# a130-8-octal-vca-expander.net
KiCad netlist of a schematic drawn in EAGLE
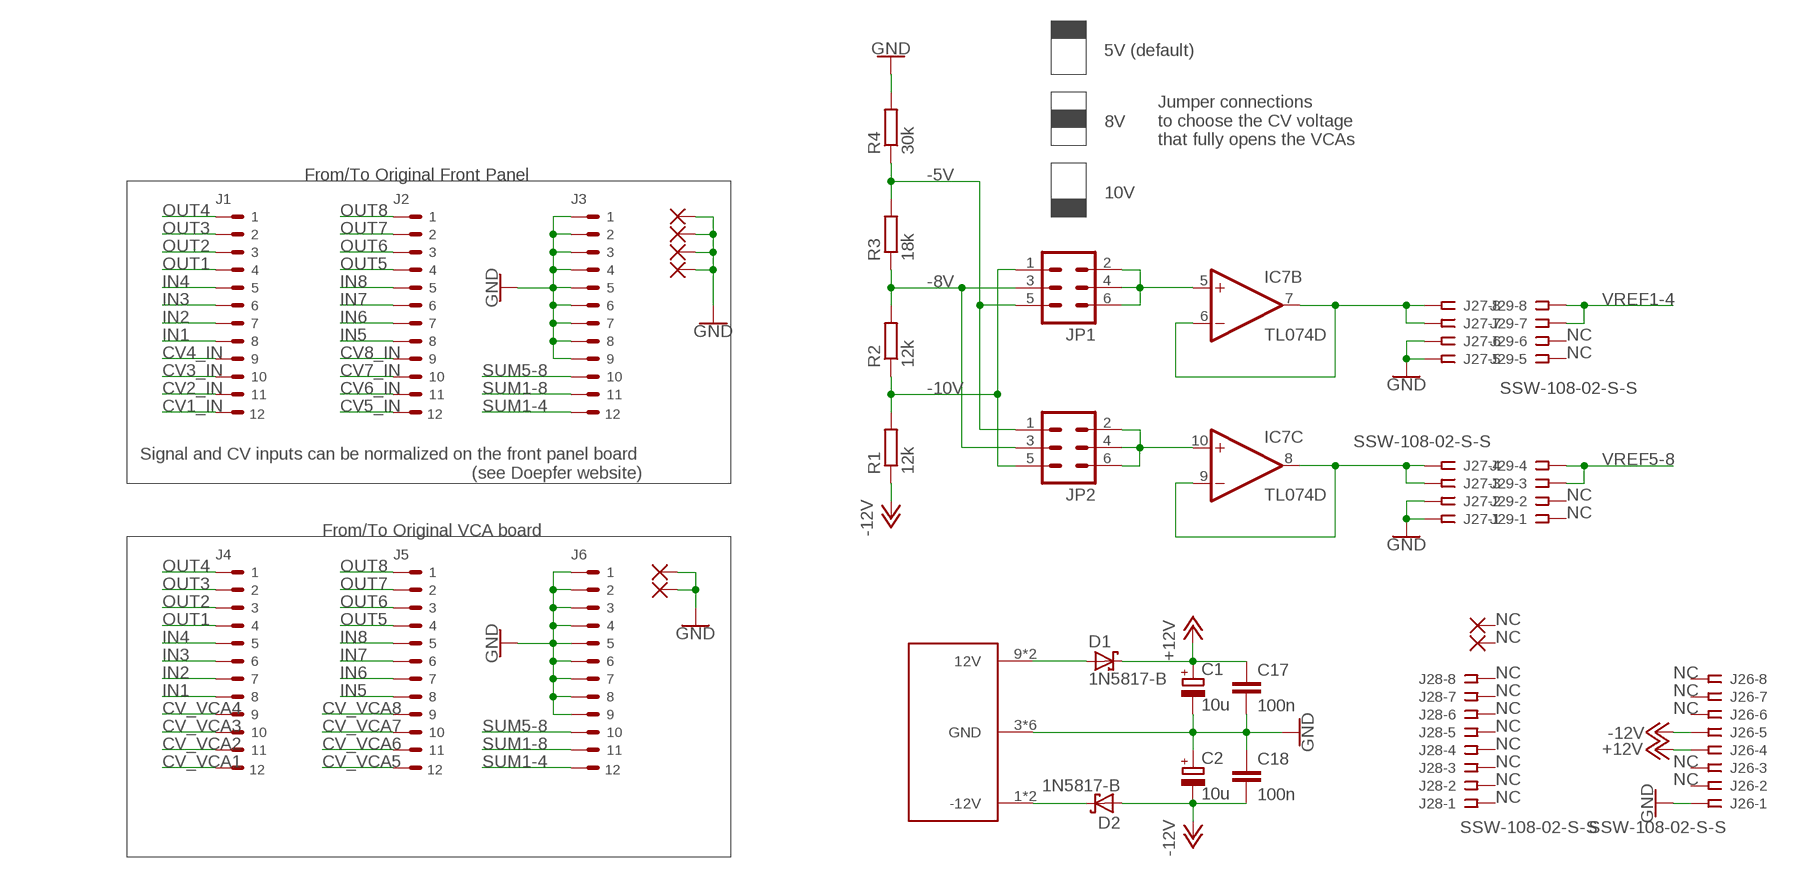
[diagram p0: schematic, sheet 1]
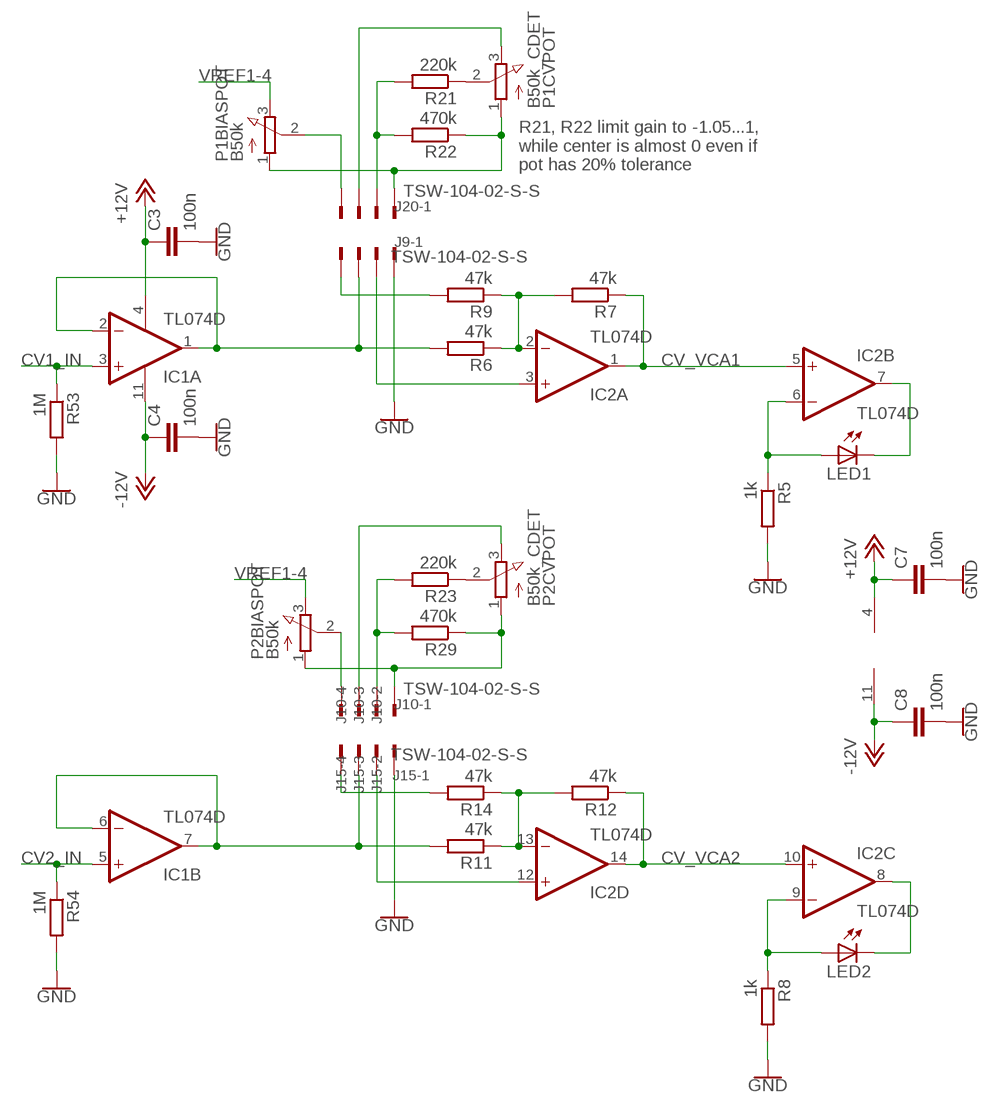
[diagram p1: schematic, sheet 2]
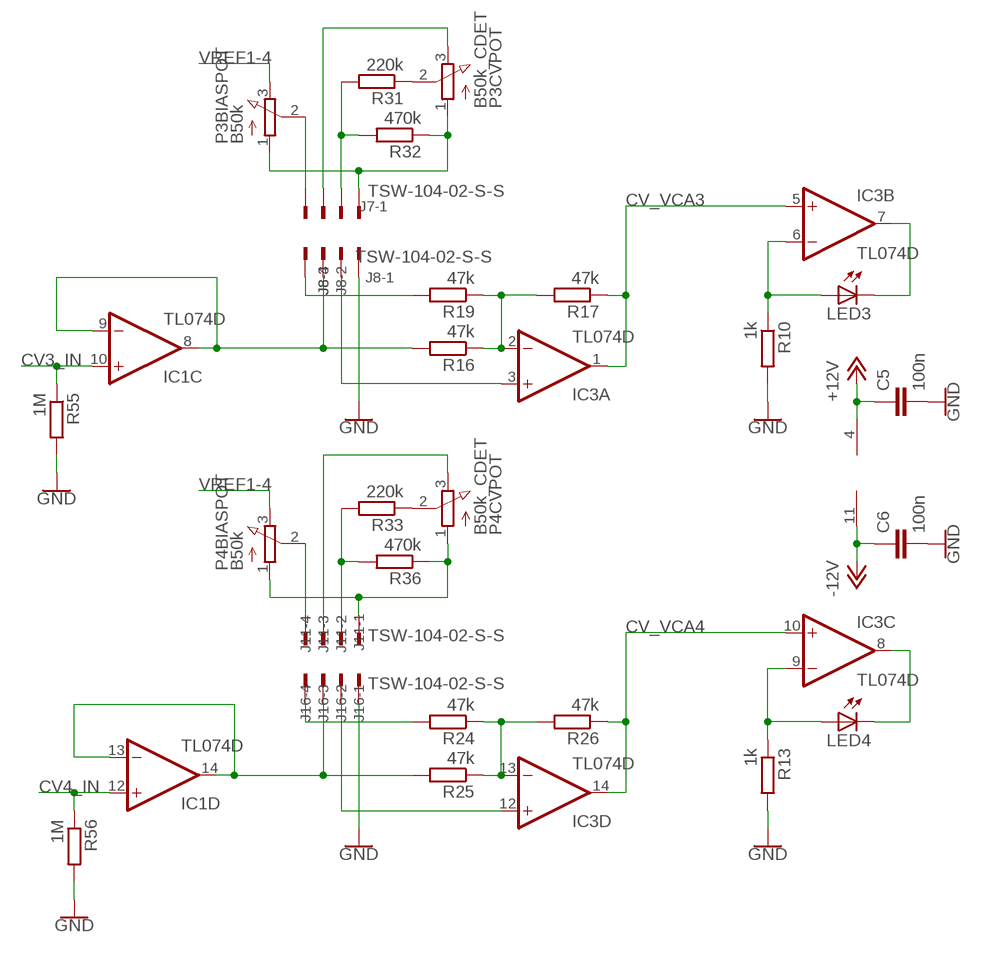
[diagram p2: schematic, sheet 3]
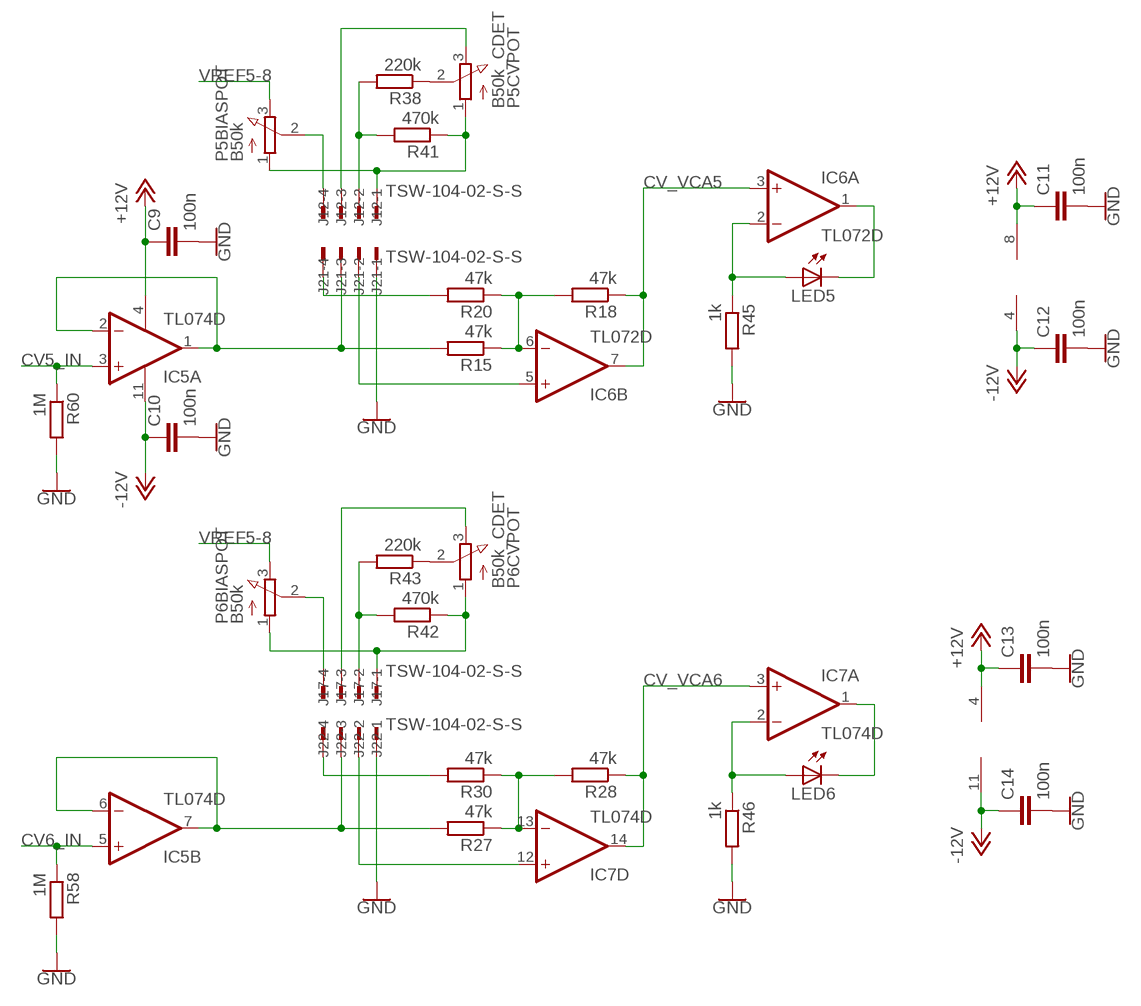
[diagram p3: schematic, sheet 4]
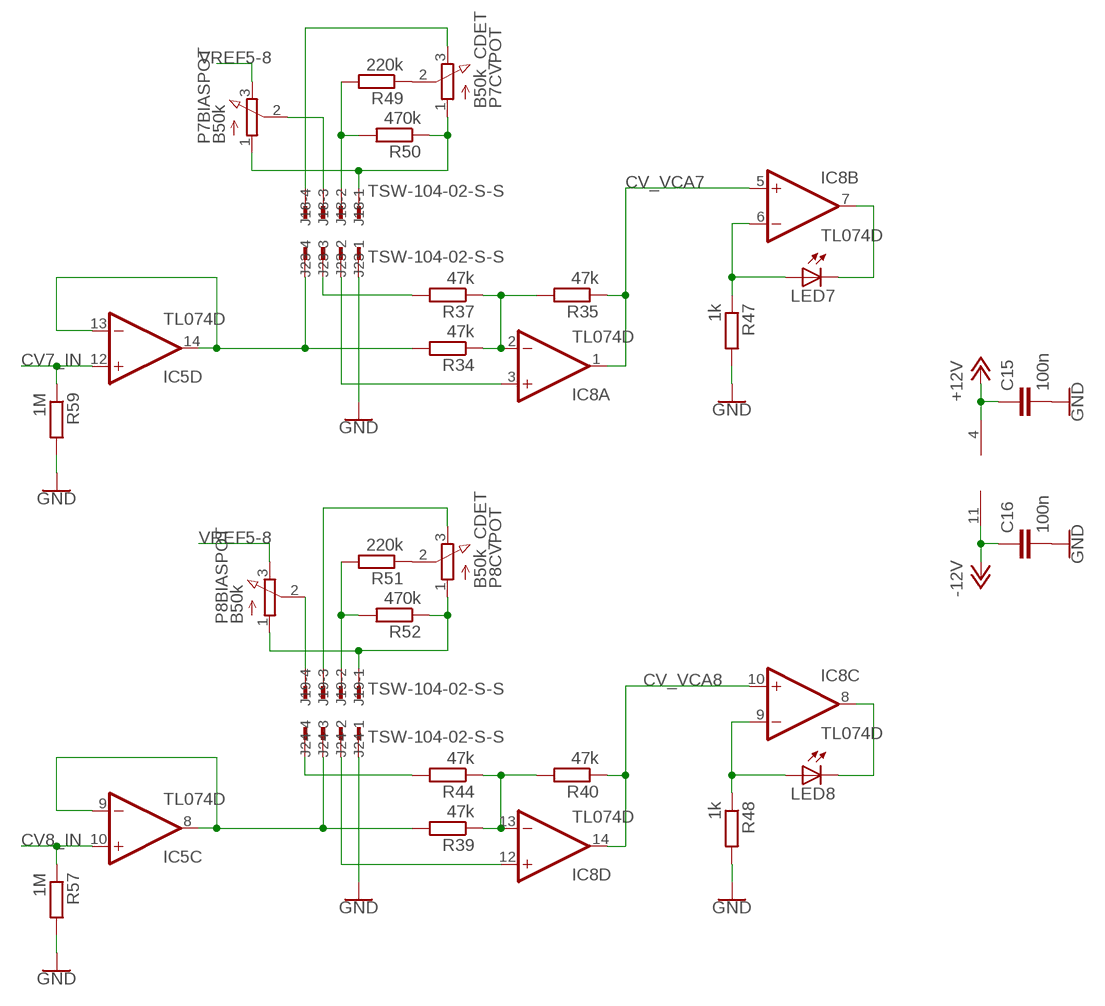
[diagram p4: schematic, sheet 5]

(export (version "E")
  (design (tool "Eeschema 10.0.6"))
  (components
    (comp (ref "C9")
      (value "100n")
      (footprint "eagle-import:C0603")
      (libsource (lib "eagle-import") (part "C-EUC0603"))
    )
    (comp (ref "C10")
      (value "100n")
      (footprint "eagle-import:C0603")
      (libsource (lib "eagle-import") (part "C-EUC0603"))
    )
    (comp (ref "C11")
      (value "100n")
      (footprint "eagle-import:C0603")
      (libsource (lib "eagle-import") (part "C-EUC0603"))
    )
    (comp (ref "C12")
      (value "100n")
      (footprint "eagle-import:C0603")
      (libsource (lib "eagle-import") (part "C-EUC0603"))
    )
    (comp (ref "C13")
      (value "100n")
      (footprint "eagle-import:C0603")
      (libsource (lib "eagle-import") (part "C-EUC0603"))
    )
    (comp (ref "C14")
      (value "100n")
      (footprint "eagle-import:C0603")
      (libsource (lib "eagle-import") (part "C-EUC0603"))
    )
    (comp (ref "IC5")
      (value "TL074D")
      (footprint "eagle-import:SO14")
      (libsource (lib "eagle-import") (part "TL074D"))
    )
    (comp (ref "IC6")
      (value "TL072D")
      (footprint "eagle-import:SO08")
      (libsource (lib "eagle-import") (part "TL072D"))
    )
    (comp (ref "IC7")
      (value "TL074D")
      (footprint "eagle-import:SO14")
      (libsource (lib "eagle-import") (part "TL074D"))
    )
    (comp (ref "J12")
      (value "TSW-104-02-S-S")
      (footprint "eagle-import:TSW-104-02-S-S")
      (libsource (lib "eagle-import") (part "TSW-104-02-S-S"))
    )
    (comp (ref "J17")
      (value "TSW-104-02-S-S")
      (footprint "eagle-import:TSW-104-02-S-S")
      (libsource (lib "eagle-import") (part "TSW-104-02-S-S"))
    )
    (comp (ref "J21")
      (value "TSW-104-02-S-S")
      (footprint "eagle-import:TSW-104-02-S-S")
      (libsource (lib "eagle-import") (part "TSW-104-02-S-S"))
    )
    (comp (ref "J22")
      (value "TSW-104-02-S-S")
      (footprint "eagle-import:TSW-104-02-S-S")
      (libsource (lib "eagle-import") (part "TSW-104-02-S-S"))
    )
    (comp (ref "LED5")
      (value "LED3MM")
      (footprint "eagle-import:LED3MM")
      (libsource (lib "eagle-import") (part "LED3MM"))
    )
    (comp (ref "LED6")
      (value "LED3MM")
      (footprint "eagle-import:LED3MM")
      (libsource (lib "eagle-import") (part "LED3MM"))
    )
    (comp (ref "P5BIAS")
      (value "B50k")
      (footprint "eagle-import:EVUF")
      (libsource (lib "eagle-import") (part "P0915N_NARROW"))
    )
    (comp (ref "P5CV")
      (value "B50k_CDET")
      (footprint "eagle-import:EVUF")
      (libsource (lib "eagle-import") (part "P0915N_NARROW"))
    )
    (comp (ref "P6BIAS")
      (value "B50k")
      (footprint "eagle-import:EVUF")
      (libsource (lib "eagle-import") (part "P0915N_NARROW"))
    )
    (comp (ref "P6CV")
      (value "B50k_CDET")
      (footprint "eagle-import:EVUF")
      (libsource (lib "eagle-import") (part "P0915N_NARROW"))
    )
    (comp (ref "R15")
      (value "47k")
      (footprint "eagle-import:M0805")
      (libsource (lib "eagle-import") (part "R-EU_M0805"))
    )
    (comp (ref "R18")
      (value "47k")
      (footprint "eagle-import:M0805")
      (libsource (lib "eagle-import") (part "R-EU_M0805"))
    )
    (comp (ref "R20")
      (value "47k")
      (footprint "eagle-import:M0805")
      (libsource (lib "eagle-import") (part "R-EU_M0805"))
    )
    (comp (ref "R27")
      (value "47k")
      (footprint "eagle-import:M0805")
      (libsource (lib "eagle-import") (part "R-EU_M0805"))
    )
    (comp (ref "R28")
      (value "47k")
      (footprint "eagle-import:M0805")
      (libsource (lib "eagle-import") (part "R-EU_M0805"))
    )
    (comp (ref "R30")
      (value "47k")
      (footprint "eagle-import:M0805")
      (libsource (lib "eagle-import") (part "R-EU_M0805"))
    )
    (comp (ref "R38")
      (value "220k")
      (footprint "eagle-import:M0805")
      (libsource (lib "eagle-import") (part "R-EU_M0805"))
    )
    (comp (ref "R41")
      (value "470k")
      (footprint "eagle-import:M0805")
      (libsource (lib "eagle-import") (part "R-EU_M0805"))
    )
    (comp (ref "R42")
      (value "470k")
      (footprint "eagle-import:M0805")
      (libsource (lib "eagle-import") (part "R-EU_M0805"))
    )
    (comp (ref "R43")
      (value "220k")
      (footprint "eagle-import:M0805")
      (libsource (lib "eagle-import") (part "R-EU_M0805"))
    )
    (comp (ref "R45")
      (value "1k")
      (footprint "eagle-import:M0805")
      (libsource (lib "eagle-import") (part "R-EU_M0805"))
    )
    (comp (ref "R46")
      (value "1k")
      (footprint "eagle-import:M0805")
      (libsource (lib "eagle-import") (part "R-EU_M0805"))
    )
    (comp (ref "R58")
      (value "1M")
      (footprint "eagle-import:M0805")
      (libsource (lib "eagle-import") (part "R-EU_M0805"))
    )
    (comp (ref "R60")
      (value "1M")
      (footprint "eagle-import:M0805")
      (libsource (lib "eagle-import") (part "R-EU_M0805"))
    )
    (comp (ref "C15")
      (value "100n")
      (footprint "eagle-import:C0603")
      (libsource (lib "eagle-import") (part "C-EUC0603"))
    )
    (comp (ref "C16")
      (value "100n")
      (footprint "eagle-import:C0603")
      (libsource (lib "eagle-import") (part "C-EUC0603"))
    )
    (comp (ref "IC8")
      (value "TL074D")
      (footprint "eagle-import:SO14")
      (libsource (lib "eagle-import") (part "TL074D"))
    )
    (comp (ref "J18")
      (value "TSW-104-02-S-S")
      (footprint "eagle-import:TSW-104-02-S-S")
      (libsource (lib "eagle-import") (part "TSW-104-02-S-S"))
    )
    (comp (ref "J19")
      (value "TSW-104-02-S-S")
      (footprint "eagle-import:TSW-104-02-S-S")
      (libsource (lib "eagle-import") (part "TSW-104-02-S-S"))
    )
    (comp (ref "J23")
      (value "TSW-104-02-S-S")
      (footprint "eagle-import:TSW-104-02-S-S")
      (libsource (lib "eagle-import") (part "TSW-104-02-S-S"))
    )
    (comp (ref "J24")
      (value "TSW-104-02-S-S")
      (footprint "eagle-import:TSW-104-02-S-S")
      (libsource (lib "eagle-import") (part "TSW-104-02-S-S"))
    )
    (comp (ref "LED7")
      (value "LED3MM")
      (footprint "eagle-import:LED3MM")
      (libsource (lib "eagle-import") (part "LED3MM"))
    )
    (comp (ref "LED8")
      (value "LED3MM")
      (footprint "eagle-import:LED3MM")
      (libsource (lib "eagle-import") (part "LED3MM"))
    )
    (comp (ref "P7BIAS")
      (value "B50k")
      (footprint "eagle-import:EVUF")
      (libsource (lib "eagle-import") (part "P0915N_NARROW"))
    )
    (comp (ref "P7CV")
      (value "B50k_CDET")
      (footprint "eagle-import:EVUF")
      (libsource (lib "eagle-import") (part "P0915N_NARROW"))
    )
    (comp (ref "P8BIAS")
      (value "B50k")
      (footprint "eagle-import:EVUF")
      (libsource (lib "eagle-import") (part "P0915N_NARROW"))
    )
    (comp (ref "P8CV")
      (value "B50k_CDET")
      (footprint "eagle-import:EVUF")
      (libsource (lib "eagle-import") (part "P0915N_NARROW"))
    )
    (comp (ref "R34")
      (value "47k")
      (footprint "eagle-import:M0805")
      (libsource (lib "eagle-import") (part "R-EU_M0805"))
    )
    (comp (ref "R35")
      (value "47k")
      (footprint "eagle-import:M0805")
      (libsource (lib "eagle-import") (part "R-EU_M0805"))
    )
    (comp (ref "R37")
      (value "47k")
      (footprint "eagle-import:M0805")
      (libsource (lib "eagle-import") (part "R-EU_M0805"))
    )
    (comp (ref "R39")
      (value "47k")
      (footprint "eagle-import:M0805")
      (libsource (lib "eagle-import") (part "R-EU_M0805"))
    )
    (comp (ref "R40")
      (value "47k")
      (footprint "eagle-import:M0805")
      (libsource (lib "eagle-import") (part "R-EU_M0805"))
    )
    (comp (ref "R44")
      (value "47k")
      (footprint "eagle-import:M0805")
      (libsource (lib "eagle-import") (part "R-EU_M0805"))
    )
    (comp (ref "R47")
      (value "1k")
      (footprint "eagle-import:M0805")
      (libsource (lib "eagle-import") (part "R-EU_M0805"))
    )
    (comp (ref "R48")
      (value "1k")
      (footprint "eagle-import:M0805")
      (libsource (lib "eagle-import") (part "R-EU_M0805"))
    )
    (comp (ref "R49")
      (value "220k")
      (footprint "eagle-import:M0805")
      (libsource (lib "eagle-import") (part "R-EU_M0805"))
    )
    (comp (ref "R50")
      (value "470k")
      (footprint "eagle-import:M0805")
      (libsource (lib "eagle-import") (part "R-EU_M0805"))
    )
    (comp (ref "R51")
      (value "220k")
      (footprint "eagle-import:M0805")
      (libsource (lib "eagle-import") (part "R-EU_M0805"))
    )
    (comp (ref "R52")
      (value "470k")
      (footprint "eagle-import:M0805")
      (libsource (lib "eagle-import") (part "R-EU_M0805"))
    )
    (comp (ref "R57")
      (value "1M")
      (footprint "eagle-import:M0805")
      (libsource (lib "eagle-import") (part "R-EU_M0805"))
    )
    (comp (ref "R59")
      (value "1M")
      (footprint "eagle-import:M0805")
      (libsource (lib "eagle-import") (part "R-EU_M0805"))
    )
    (comp (ref "C5")
      (value "100n")
      (footprint "eagle-import:C0603")
      (libsource (lib "eagle-import") (part "C-EUC0603"))
    )
    (comp (ref "C6")
      (value "100n")
      (footprint "eagle-import:C0603")
      (libsource (lib "eagle-import") (part "C-EUC0603"))
    )
    (comp (ref "IC1")
      (value "TL074D")
      (footprint "eagle-import:SO14")
      (libsource (lib "eagle-import") (part "TL074D"))
    )
    (comp (ref "IC2")
      (value "TL074D")
      (footprint "eagle-import:SO14")
      (libsource (lib "eagle-import") (part "TL074D"))
    )
    (comp (ref "IC3")
      (value "TL074D")
      (footprint "eagle-import:SO14")
      (libsource (lib "eagle-import") (part "TL074D"))
    )
    (comp (ref "J7")
      (value "TSW-104-02-S-S")
      (footprint "eagle-import:TSW-104-02-S-S")
      (libsource (lib "eagle-import") (part "TSW-104-02-S-S"))
    )
    (comp (ref "J8")
      (value "TSW-104-02-S-S")
      (footprint "eagle-import:TSW-104-02-S-S")
      (libsource (lib "eagle-import") (part "TSW-104-02-S-S"))
    )
    (comp (ref "J11")
      (value "TSW-104-02-S-S")
      (footprint "eagle-import:TSW-104-02-S-S")
      (libsource (lib "eagle-import") (part "TSW-104-02-S-S"))
    )
    (comp (ref "J16")
      (value "TSW-104-02-S-S")
      (footprint "eagle-import:TSW-104-02-S-S")
      (libsource (lib "eagle-import") (part "TSW-104-02-S-S"))
    )
    (comp (ref "LED3")
      (value "LED3MM")
      (footprint "eagle-import:LED3MM")
      (libsource (lib "eagle-import") (part "LED3MM"))
    )
    (comp (ref "LED4")
      (value "LED3MM")
      (footprint "eagle-import:LED3MM")
      (libsource (lib "eagle-import") (part "LED3MM"))
    )
    (comp (ref "P3BIAS")
      (value "B50k")
      (footprint "eagle-import:EVUF")
      (libsource (lib "eagle-import") (part "P0915N_NARROW"))
    )
    (comp (ref "P3CV")
      (value "B50k_CDET")
      (footprint "eagle-import:EVUF")
      (libsource (lib "eagle-import") (part "P0915N_NARROW"))
    )
    (comp (ref "P4BIAS")
      (value "B50k")
      (footprint "eagle-import:EVUF")
      (libsource (lib "eagle-import") (part "P0915N_NARROW"))
    )
    (comp (ref "P4CV")
      (value "B50k_CDET")
      (footprint "eagle-import:EVUF")
      (libsource (lib "eagle-import") (part "P0915N_NARROW"))
    )
    (comp (ref "R10")
      (value "1k")
      (footprint "eagle-import:M0805")
      (libsource (lib "eagle-import") (part "R-EU_M0805"))
    )
    (comp (ref "R13")
      (value "1k")
      (footprint "eagle-import:M0805")
      (libsource (lib "eagle-import") (part "R-EU_M0805"))
    )
    (comp (ref "R16")
      (value "47k")
      (footprint "eagle-import:M0805")
      (libsource (lib "eagle-import") (part "R-EU_M0805"))
    )
    (comp (ref "R17")
      (value "47k")
      (footprint "eagle-import:M0805")
      (libsource (lib "eagle-import") (part "R-EU_M0805"))
    )
    (comp (ref "R19")
      (value "47k")
      (footprint "eagle-import:M0805")
      (libsource (lib "eagle-import") (part "R-EU_M0805"))
    )
    (comp (ref "R24")
      (value "47k")
      (footprint "eagle-import:M0805")
      (libsource (lib "eagle-import") (part "R-EU_M0805"))
    )
    (comp (ref "R25")
      (value "47k")
      (footprint "eagle-import:M0805")
      (libsource (lib "eagle-import") (part "R-EU_M0805"))
    )
    (comp (ref "R26")
      (value "47k")
      (footprint "eagle-import:M0805")
      (libsource (lib "eagle-import") (part "R-EU_M0805"))
    )
    (comp (ref "R31")
      (value "220k")
      (footprint "eagle-import:M0805")
      (libsource (lib "eagle-import") (part "R-EU_M0805"))
    )
    (comp (ref "R32")
      (value "470k")
      (footprint "eagle-import:M0805")
      (libsource (lib "eagle-import") (part "R-EU_M0805"))
    )
    (comp (ref "R33")
      (value "220k")
      (footprint "eagle-import:M0805")
      (libsource (lib "eagle-import") (part "R-EU_M0805"))
    )
    (comp (ref "R36")
      (value "470k")
      (footprint "eagle-import:M0805")
      (libsource (lib "eagle-import") (part "R-EU_M0805"))
    )
    (comp (ref "R55")
      (value "1M")
      (footprint "eagle-import:M0805")
      (libsource (lib "eagle-import") (part "R-EU_M0805"))
    )
    (comp (ref "R56")
      (value "1M")
      (footprint "eagle-import:M0805")
      (libsource (lib "eagle-import") (part "R-EU_M0805"))
    )
    (comp (ref "C3")
      (value "100n")
      (footprint "eagle-import:C0603")
      (libsource (lib "eagle-import") (part "C-EUC0603"))
    )
    (comp (ref "C4")
      (value "100n")
      (footprint "eagle-import:C0603")
      (libsource (lib "eagle-import") (part "C-EUC0603"))
    )
    (comp (ref "C7")
      (value "100n")
      (footprint "eagle-import:C0603")
      (libsource (lib "eagle-import") (part "C-EUC0603"))
    )
    (comp (ref "C8")
      (value "100n")
      (footprint "eagle-import:C0603")
      (libsource (lib "eagle-import") (part "C-EUC0603"))
    )
    (comp (ref "J9")
      (value "TSW-104-02-S-S")
      (footprint "eagle-import:TSW-104-02-S-S")
      (libsource (lib "eagle-import") (part "TSW-104-02-S-S"))
    )
    (comp (ref "J10")
      (value "TSW-104-02-S-S")
      (footprint "eagle-import:TSW-104-02-S-S")
      (libsource (lib "eagle-import") (part "TSW-104-02-S-S"))
    )
    (comp (ref "J15")
      (value "TSW-104-02-S-S")
      (footprint "eagle-import:TSW-104-02-S-S")
      (libsource (lib "eagle-import") (part "TSW-104-02-S-S"))
    )
    (comp (ref "J20")
      (value "TSW-104-02-S-S")
      (footprint "eagle-import:TSW-104-02-S-S")
      (libsource (lib "eagle-import") (part "TSW-104-02-S-S"))
    )
    (comp (ref "LED1")
      (value "LED3MM")
      (footprint "eagle-import:LED3MM")
      (libsource (lib "eagle-import") (part "LED3MM"))
    )
    (comp (ref "LED2")
      (value "LED3MM")
      (footprint "eagle-import:LED3MM")
      (libsource (lib "eagle-import") (part "LED3MM"))
    )
    (comp (ref "P1BIAS")
      (value "B50k")
      (footprint "eagle-import:EVUF")
      (libsource (lib "eagle-import") (part "P0915N_NARROW"))
    )
    (comp (ref "P1CV")
      (value "B50k_CDET")
      (footprint "eagle-import:EVUF")
      (libsource (lib "eagle-import") (part "P0915N_NARROW"))
    )
    (comp (ref "P2BIAS")
      (value "B50k")
      (footprint "eagle-import:EVUF")
      (libsource (lib "eagle-import") (part "P0915N_NARROW"))
    )
    (comp (ref "P2CV")
      (value "B50k_CDET")
      (footprint "eagle-import:EVUF")
      (libsource (lib "eagle-import") (part "P0915N_NARROW"))
    )
    (comp (ref "R5")
      (value "1k")
      (footprint "eagle-import:M0805")
      (libsource (lib "eagle-import") (part "R-EU_M0805"))
    )
    (comp (ref "R6")
      (value "47k")
      (footprint "eagle-import:M0805")
      (libsource (lib "eagle-import") (part "R-EU_M0805"))
    )
    (comp (ref "R7")
      (value "47k")
      (footprint "eagle-import:M0805")
      (libsource (lib "eagle-import") (part "R-EU_M0805"))
    )
    (comp (ref "R8")
      (value "1k")
      (footprint "eagle-import:M0805")
      (libsource (lib "eagle-import") (part "R-EU_M0805"))
    )
    (comp (ref "R9")
      (value "47k")
      (footprint "eagle-import:M0805")
      (libsource (lib "eagle-import") (part "R-EU_M0805"))
    )
    (comp (ref "R11")
      (value "47k")
      (footprint "eagle-import:M0805")
      (libsource (lib "eagle-import") (part "R-EU_M0805"))
    )
    (comp (ref "R12")
      (value "47k")
      (footprint "eagle-import:M0805")
      (libsource (lib "eagle-import") (part "R-EU_M0805"))
    )
    (comp (ref "R14")
      (value "47k")
      (footprint "eagle-import:M0805")
      (libsource (lib "eagle-import") (part "R-EU_M0805"))
    )
    (comp (ref "R21")
      (value "220k")
      (footprint "eagle-import:M0805")
      (libsource (lib "eagle-import") (part "R-EU_M0805"))
    )
    (comp (ref "R22")
      (value "470k")
      (footprint "eagle-import:M0805")
      (libsource (lib "eagle-import") (part "R-EU_M0805"))
    )
    (comp (ref "R23")
      (value "220k")
      (footprint "eagle-import:M0805")
      (libsource (lib "eagle-import") (part "R-EU_M0805"))
    )
    (comp (ref "R29")
      (value "470k")
      (footprint "eagle-import:M0805")
      (libsource (lib "eagle-import") (part "R-EU_M0805"))
    )
    (comp (ref "R53")
      (value "1M")
      (footprint "eagle-import:M0805")
      (libsource (lib "eagle-import") (part "R-EU_M0805"))
    )
    (comp (ref "R54")
      (value "1M")
      (footprint "eagle-import:M0805")
      (libsource (lib "eagle-import") (part "R-EU_M0805"))
    )
    (comp (ref "C1")
      (value "10u")
      (footprint "eagle-import:E2-5")
      (libsource (lib "eagle-import") (part "CPOL-EUE2-5"))
    )
    (comp (ref "C2")
      (value "10u")
      (footprint "eagle-import:E2-5")
      (libsource (lib "eagle-import") (part "CPOL-EUE2-5"))
    )
    (comp (ref "C17")
      (value "100n")
      (footprint "eagle-import:C0603")
      (libsource (lib "eagle-import") (part "C-EUC0603"))
    )
    (comp (ref "C18")
      (value "100n")
      (footprint "eagle-import:C0603")
      (libsource (lib "eagle-import") (part "C-EUC0603"))
    )
    (comp (ref "D1")
      (value "1N5817-B")
      (footprint "eagle-import:DO41-7.6")
      (libsource (lib "eagle-import") (part "1N5817-B"))
    )
    (comp (ref "D2")
      (value "1N5817-B")
      (footprint "eagle-import:DO41-7.6")
      (libsource (lib "eagle-import") (part "1N5817-B"))
    )
    (comp (ref "J1")
      (value "PIN_HEADER_1X12_2MM_GRID")
      (footprint "eagle-import:PIN_HEADER_1X12_2MM_GRID")
      (libsource (lib "eagle-import") (part "PIN_HEADER_1X12_2MM_GRID"))
    )
    (comp (ref "J2")
      (value "PIN_HEADER_1X12_2MM_GRID")
      (footprint "eagle-import:PIN_HEADER_1X12_2MM_GRID")
      (libsource (lib "eagle-import") (part "PIN_HEADER_1X12_2MM_GRID"))
    )
    (comp (ref "J3")
      (value "PIN_HEADER_1X12_2MM_GRID")
      (footprint "eagle-import:PIN_HEADER_1X12_2MM_GRID")
      (libsource (lib "eagle-import") (part "PIN_HEADER_1X12_2MM_GRID"))
    )
    (comp (ref "J4")
      (value "PIN_HEADER_1X12_2MM_GRID")
      (footprint "eagle-import:PIN_HEADER_1X12_2MM_GRID")
      (libsource (lib "eagle-import") (part "PIN_HEADER_1X12_2MM_GRID"))
    )
    (comp (ref "J5")
      (value "PIN_HEADER_1X12_2MM_GRID")
      (footprint "eagle-import:PIN_HEADER_1X12_2MM_GRID")
      (libsource (lib "eagle-import") (part "PIN_HEADER_1X12_2MM_GRID"))
    )
    (comp (ref "J6")
      (value "PIN_HEADER_1X12_2MM_GRID")
      (footprint "eagle-import:PIN_HEADER_1X12_2MM_GRID")
      (libsource (lib "eagle-import") (part "PIN_HEADER_1X12_2MM_GRID"))
    )
    (comp (ref "J25")
      (value "A100-BUS_HEADER_10P")
      (footprint "eagle-import:DOEPFER_2X05")
      (libsource (lib "eagle-import") (part "A100-BUS_HEADER_10P"))
    )
    (comp (ref "J26")
      (value "SSW-108-02-S-S")
      (footprint "eagle-import:SSW-108-02-S-S")
      (libsource (lib "eagle-import") (part "SSW-108-02-S-S"))
    )
    (comp (ref "J27")
      (value "SSW-108-02-S-S")
      (footprint "eagle-import:SSW-108-02-S-S")
      (libsource (lib "eagle-import") (part "SSW-108-02-S-S"))
    )
    (comp (ref "J28")
      (value "SSW-108-02-S-S")
      (footprint "eagle-import:SSW-108-02-S-S")
      (libsource (lib "eagle-import") (part "SSW-108-02-S-S"))
    )
    (comp (ref "J29")
      (value "SSW-108-02-S-S")
      (footprint "eagle-import:SSW-108-02-S-S")
      (libsource (lib "eagle-import") (part "SSW-108-02-S-S"))
    )
    (comp (ref "JP1")
      (value "MA03-2")
      (footprint "eagle-import:MA03-2")
      (libsource (lib "eagle-import") (part "MA03-2"))
    )
    (comp (ref "JP2")
      (value "MA03-2")
      (footprint "eagle-import:MA03-2")
      (libsource (lib "eagle-import") (part "MA03-2"))
    )
    (comp (ref "PAD1")
      (value "2,15/1,0")
      (footprint "eagle-import:2,15_1,0")
      (libsource (lib "eagle-import") (part "2,15/1,0"))
    )
    (comp (ref "PAD2")
      (value "2,15/1,0")
      (footprint "eagle-import:2,15_1,0")
      (libsource (lib "eagle-import") (part "2,15/1,0"))
    )
    (comp (ref "PAD3")
      (value "2,15/1,0")
      (footprint "eagle-import:2,15_1,0")
      (libsource (lib "eagle-import") (part "2,15/1,0"))
    )
    (comp (ref "PAD4")
      (value "2,15/1,0")
      (footprint "eagle-import:2,15_1,0")
      (libsource (lib "eagle-import") (part "2,15/1,0"))
    )
    (comp (ref "PAD5")
      (value "2,15/1,0")
      (footprint "eagle-import:2,15_1,0")
      (libsource (lib "eagle-import") (part "2,15/1,0"))
    )
    (comp (ref "PAD6")
      (value "2,15/1,0")
      (footprint "eagle-import:2,15_1,0")
      (libsource (lib "eagle-import") (part "2,15/1,0"))
    )
    (comp (ref "PAD7")
      (value "2,15/1,0")
      (footprint "eagle-import:2,15_1,0")
      (libsource (lib "eagle-import") (part "2,15/1,0"))
    )
    (comp (ref "PAD9")
      (value "2,15/1,0")
      (footprint "eagle-import:2,15_1,0")
      (libsource (lib "eagle-import") (part "2,15/1,0"))
    )
    (comp (ref "R1")
      (value "12k")
      (footprint "eagle-import:M0805")
      (libsource (lib "eagle-import") (part "R-EU_M0805"))
    )
    (comp (ref "R2")
      (value "12k")
      (footprint "eagle-import:M0805")
      (libsource (lib "eagle-import") (part "R-EU_M0805"))
    )
    (comp (ref "R3")
      (value "18k")
      (footprint "eagle-import:M0805")
      (libsource (lib "eagle-import") (part "R-EU_M0805"))
    )
    (comp (ref "R4")
      (value "30k")
      (footprint "eagle-import:M0805")
      (libsource (lib "eagle-import") (part "R-EU_M0805"))
    )
  )
  (nets
    (net (code "1") (name "+12V") (class "Default")
      (node (ref "C1") (pin "+") (pinfunction "+_+") (pintype "passive"))
      (node (ref "C11") (pin "1") (pinfunction "1_1") (pintype "passive"))
      (node (ref "C13") (pin "1") (pinfunction "1_1") (pintype "passive"))
      (node (ref "C15") (pin "1") (pinfunction "1_1") (pintype "passive"))
      (node (ref "C17") (pin "1") (pinfunction "1_1") (pintype "passive"))
      (node (ref "C3") (pin "1") (pinfunction "1_1") (pintype "passive"))
      (node (ref "C5") (pin "1") (pinfunction "1_1") (pintype "passive"))
      (node (ref "C7") (pin "1") (pinfunction "1_1") (pintype "passive"))
      (node (ref "C9") (pin "1") (pinfunction "1_1") (pintype "passive"))
      (node (ref "D1") (pin "C") (pinfunction "C_C") (pintype "passive"))
      (node (ref "IC1") (pin "4") (pinfunction "V+_4") (pintype "power_in"))
      (node (ref "IC2") (pin "4") (pinfunction "V+_4") (pintype "power_in"))
      (node (ref "IC3") (pin "4") (pinfunction "V+_4") (pintype "power_in"))
      (node (ref "IC5") (pin "4") (pinfunction "V+_4") (pintype "power_in"))
      (node (ref "IC6") (pin "8") (pinfunction "V+_8") (pintype "power_in"))
      (node (ref "IC7") (pin "4") (pinfunction "V+_4") (pintype "power_in"))
      (node (ref "IC8") (pin "4") (pinfunction "V+_4") (pintype "power_in"))
      (node (ref "J26") (pin "4") (pinfunction "1_4") (pintype "passive"))
    )
    (net (code "2") (name "-5V") (class "Default")
      (node (ref "JP1") (pin "5") (pinfunction "5_5") (pintype "passive"))
      (node (ref "JP2") (pin "1") (pinfunction "1_1") (pintype "passive"))
      (node (ref "R3") (pin "2") (pinfunction "2_2") (pintype "passive"))
      (node (ref "R4") (pin "1") (pinfunction "1_1") (pintype "passive"))
    )
    (net (code "3") (name "-8V") (class "Default")
      (node (ref "JP1") (pin "3") (pinfunction "3_3") (pintype "passive"))
      (node (ref "JP2") (pin "3") (pinfunction "3_3") (pintype "passive"))
      (node (ref "R2") (pin "2") (pinfunction "2_2") (pintype "passive"))
      (node (ref "R3") (pin "1") (pinfunction "1_1") (pintype "passive"))
    )
    (net (code "4") (name "-10V") (class "Default")
      (node (ref "JP1") (pin "1") (pinfunction "1_1") (pintype "passive"))
      (node (ref "JP2") (pin "5") (pinfunction "5_5") (pintype "passive"))
      (node (ref "R1") (pin "2") (pinfunction "2_2") (pintype "passive"))
      (node (ref "R2") (pin "1") (pinfunction "1_1") (pintype "passive"))
    )
    (net (code "5") (name "-12V") (class "Default")
      (node (ref "C10") (pin "1") (pinfunction "1_1") (pintype "passive"))
      (node (ref "C12") (pin "1") (pinfunction "1_1") (pintype "passive"))
      (node (ref "C14") (pin "1") (pinfunction "1_1") (pintype "passive"))
      (node (ref "C16") (pin "1") (pinfunction "1_1") (pintype "passive"))
      (node (ref "C18") (pin "2") (pinfunction "2_2") (pintype "passive"))
      (node (ref "C2") (pin "-") (pinfunction "-_-") (pintype "passive"))
      (node (ref "C4") (pin "1") (pinfunction "1_1") (pintype "passive"))
      (node (ref "C6") (pin "1") (pinfunction "1_1") (pintype "passive"))
      (node (ref "C8") (pin "1") (pinfunction "1_1") (pintype "passive"))
      (node (ref "D2") (pin "A") (pinfunction "A_A") (pintype "passive"))
      (node (ref "IC1") (pin "11") (pinfunction "V-_11") (pintype "power_in"))
      (node (ref "IC2") (pin "11") (pinfunction "V-_11") (pintype "power_in"))
      (node (ref "IC3") (pin "11") (pinfunction "V-_11") (pintype "power_in"))
      (node (ref "IC5") (pin "11") (pinfunction "V-_11") (pintype "power_in"))
      (node (ref "IC6") (pin "4") (pinfunction "V-_4") (pintype "power_in"))
      (node (ref "IC7") (pin "11") (pinfunction "V-_11") (pintype "power_in"))
      (node (ref "IC8") (pin "11") (pinfunction "V-_11") (pintype "power_in"))
      (node (ref "J26") (pin "5") (pinfunction "1_5") (pintype "passive"))
      (node (ref "R1") (pin "1") (pinfunction "1_1") (pintype "passive"))
    )
    (net (code "6") (name "CV1_IN") (class "Default")
      (node (ref "IC1") (pin "3") (pinfunction "+IN_3") (pintype "input"))
      (node (ref "J1") (pin "12") (pinfunction "S11_12") (pintype "passive"))
      (node (ref "R53") (pin "1") (pinfunction "1_1") (pintype "passive"))
    )
    (net (code "7") (name "CV2_IN") (class "Default")
      (node (ref "IC1") (pin "5") (pinfunction "+IN_5") (pintype "input"))
      (node (ref "J1") (pin "11") (pinfunction "S10_11") (pintype "passive"))
      (node (ref "R54") (pin "1") (pinfunction "1_1") (pintype "passive"))
    )
    (net (code "8") (name "CV3_IN") (class "Default")
      (node (ref "IC1") (pin "10") (pinfunction "+IN_10") (pintype "input"))
      (node (ref "J1") (pin "10") (pinfunction "S9_10") (pintype "passive"))
      (node (ref "R55") (pin "1") (pinfunction "1_1") (pintype "passive"))
    )
    (net (code "9") (name "CV4_IN") (class "Default")
      (node (ref "IC1") (pin "12") (pinfunction "+IN_12") (pintype "input"))
      (node (ref "J1") (pin "9") (pinfunction "S8_9") (pintype "passive"))
      (node (ref "R56") (pin "1") (pinfunction "1_1") (pintype "passive"))
    )
    (net (code "10") (name "CV5_IN") (class "Default")
      (node (ref "IC5") (pin "3") (pinfunction "+IN_3") (pintype "input"))
      (node (ref "J2") (pin "12") (pinfunction "S11_12") (pintype "passive"))
      (node (ref "R60") (pin "1") (pinfunction "1_1") (pintype "passive"))
    )
    (net (code "11") (name "CV6_IN") (class "Default")
      (node (ref "IC5") (pin "5") (pinfunction "+IN_5") (pintype "input"))
      (node (ref "J2") (pin "11") (pinfunction "S10_11") (pintype "passive"))
      (node (ref "R58") (pin "1") (pinfunction "1_1") (pintype "passive"))
    )
    (net (code "12") (name "CV7_IN") (class "Default")
      (node (ref "IC5") (pin "12") (pinfunction "+IN_12") (pintype "input"))
      (node (ref "J2") (pin "10") (pinfunction "S9_10") (pintype "passive"))
      (node (ref "R59") (pin "1") (pinfunction "1_1") (pintype "passive"))
    )
    (net (code "13") (name "CV8_IN") (class "Default")
      (node (ref "IC5") (pin "10") (pinfunction "+IN_10") (pintype "input"))
      (node (ref "J2") (pin "9") (pinfunction "S8_9") (pintype "passive"))
      (node (ref "R57") (pin "1") (pinfunction "1_1") (pintype "passive"))
    )
    (net (code "14") (name "CV_VCA1") (class "Default")
      (node (ref "IC2") (pin "1") (pinfunction "OUT_1") (pintype "output"))
      (node (ref "IC2") (pin "5") (pinfunction "+IN_5") (pintype "input"))
      (node (ref "J4") (pin "12") (pinfunction "S11_12") (pintype "passive"))
      (node (ref "R7") (pin "1") (pinfunction "1_1") (pintype "passive"))
    )
    (net (code "15") (name "CV_VCA2") (class "Default")
      (node (ref "IC2") (pin "10") (pinfunction "+IN_10") (pintype "input"))
      (node (ref "IC2") (pin "14") (pinfunction "OUT_14") (pintype "output"))
      (node (ref "J4") (pin "11") (pinfunction "S10_11") (pintype "passive"))
      (node (ref "R12") (pin "1") (pinfunction "1_1") (pintype "passive"))
    )
    (net (code "16") (name "CV_VCA3") (class "Default")
      (node (ref "IC3") (pin "1") (pinfunction "OUT_1") (pintype "output"))
      (node (ref "IC3") (pin "5") (pinfunction "+IN_5") (pintype "input"))
      (node (ref "J4") (pin "10") (pinfunction "S9_10") (pintype "passive"))
      (node (ref "R17") (pin "1") (pinfunction "1_1") (pintype "passive"))
    )
    (net (code "17") (name "CV_VCA4") (class "Default")
      (node (ref "IC3") (pin "10") (pinfunction "+IN_10") (pintype "input"))
      (node (ref "IC3") (pin "14") (pinfunction "OUT_14") (pintype "output"))
      (node (ref "J4") (pin "9") (pinfunction "S8_9") (pintype "passive"))
      (node (ref "R26") (pin "1") (pinfunction "1_1") (pintype "passive"))
    )
    (net (code "18") (name "CV_VCA5") (class "Default")
      (node (ref "IC6") (pin "3") (pinfunction "+IN_3") (pintype "input"))
      (node (ref "IC6") (pin "7") (pinfunction "OUT_7") (pintype "output"))
      (node (ref "J5") (pin "12") (pinfunction "S11_12") (pintype "passive"))
      (node (ref "R18") (pin "1") (pinfunction "1_1") (pintype "passive"))
    )
    (net (code "19") (name "CV_VCA6") (class "Default")
      (node (ref "IC7") (pin "14") (pinfunction "OUT_14") (pintype "output"))
      (node (ref "IC7") (pin "3") (pinfunction "+IN_3") (pintype "input"))
      (node (ref "J5") (pin "11") (pinfunction "S10_11") (pintype "passive"))
      (node (ref "R28") (pin "1") (pinfunction "1_1") (pintype "passive"))
    )
    (net (code "20") (name "CV_VCA7") (class "Default")
      (node (ref "IC8") (pin "1") (pinfunction "OUT_1") (pintype "output"))
      (node (ref "IC8") (pin "5") (pinfunction "+IN_5") (pintype "input"))
      (node (ref "J5") (pin "10") (pinfunction "S9_10") (pintype "passive"))
      (node (ref "R35") (pin "1") (pinfunction "1_1") (pintype "passive"))
    )
    (net (code "21") (name "CV_VCA8") (class "Default")
      (node (ref "IC8") (pin "10") (pinfunction "+IN_10") (pintype "input"))
      (node (ref "IC8") (pin "14") (pinfunction "OUT_14") (pintype "output"))
      (node (ref "J5") (pin "9") (pinfunction "S8_9") (pintype "passive"))
      (node (ref "R40") (pin "1") (pinfunction "1_1") (pintype "passive"))
    )
    (net (code "22") (name "GND") (class "Default")
      (node (ref "C1") (pin "-") (pinfunction "-_-") (pintype "passive"))
      (node (ref "C10") (pin "2") (pinfunction "2_2") (pintype "passive"))
      (node (ref "C11") (pin "2") (pinfunction "2_2") (pintype "passive"))
      (node (ref "C12") (pin "2") (pinfunction "2_2") (pintype "passive"))
      (node (ref "C13") (pin "2") (pinfunction "2_2") (pintype "passive"))
      (node (ref "C14") (pin "2") (pinfunction "2_2") (pintype "passive"))
      (node (ref "C15") (pin "2") (pinfunction "2_2") (pintype "passive"))
      (node (ref "C16") (pin "2") (pinfunction "2_2") (pintype "passive"))
      (node (ref "C17") (pin "2") (pinfunction "2_2") (pintype "passive"))
      (node (ref "C18") (pin "1") (pinfunction "1_1") (pintype "passive"))
      (node (ref "C2") (pin "+") (pinfunction "+_+") (pintype "passive"))
      (node (ref "C3") (pin "2") (pinfunction "2_2") (pintype "passive"))
      (node (ref "C4") (pin "2") (pinfunction "2_2") (pintype "passive"))
      (node (ref "C5") (pin "2") (pinfunction "2_2") (pintype "passive"))
      (node (ref "C6") (pin "2") (pinfunction "2_2") (pintype "passive"))
      (node (ref "C7") (pin "2") (pinfunction "2_2") (pintype "passive"))
      (node (ref "C8") (pin "2") (pinfunction "2_2") (pintype "passive"))
      (node (ref "C9") (pin "2") (pinfunction "2_2") (pintype "passive"))
      (node (ref "J15") (pin "1") (pinfunction "1_1") (pintype "passive"))
      (node (ref "J16") (pin "1") (pinfunction "1_1") (pintype "passive"))
      (node (ref "J20") (pin "1") (pinfunction "1_1") (pintype "passive"))
      (node (ref "J21") (pin "1") (pinfunction "1_1") (pintype "passive"))
      (node (ref "J22") (pin "1") (pinfunction "1_1") (pintype "passive"))
      (node (ref "J23") (pin "1") (pinfunction "1_1") (pintype "passive"))
      (node (ref "J24") (pin "1") (pinfunction "1_1") (pintype "passive"))
      (node (ref "J25") (pin "3") (pinfunction "GND_3") (pintype "power_in"))
      (node (ref "J25") (pin "4") (pinfunction "GND_4") (pintype "power_in"))
      (node (ref "J25") (pin "5") (pinfunction "GND_5") (pintype "power_in"))
      (node (ref "J25") (pin "6") (pinfunction "GND_6") (pintype "power_in"))
      (node (ref "J25") (pin "7") (pinfunction "GND_7") (pintype "power_in"))
      (node (ref "J25") (pin "8") (pinfunction "GND_8") (pintype "power_in"))
      (node (ref "J26") (pin "1") (pinfunction "1_1") (pintype "passive"))
      (node (ref "J27") (pin "1") (pinfunction "1_1") (pintype "passive"))
      (node (ref "J27") (pin "2") (pinfunction "1_2") (pintype "passive"))
      (node (ref "J27") (pin "5") (pinfunction "1_5") (pintype "passive"))
      (node (ref "J27") (pin "6") (pinfunction "1_6") (pintype "passive"))
      (node (ref "J3") (pin "1") (pinfunction "S1_1") (pintype "passive"))
      (node (ref "J3") (pin "2") (pinfunction "S2_2") (pintype "passive"))
      (node (ref "J3") (pin "3") (pinfunction "S3_3") (pintype "passive"))
      (node (ref "J3") (pin "4") (pinfunction "S4_4") (pintype "passive"))
      (node (ref "J3") (pin "5") (pinfunction "S_5") (pintype "passive"))
      (node (ref "J3") (pin "6") (pinfunction "S5_6") (pintype "passive"))
      (node (ref "J3") (pin "7") (pinfunction "S6_7") (pintype "passive"))
      (node (ref "J3") (pin "8") (pinfunction "S7_8") (pintype "passive"))
      (node (ref "J3") (pin "9") (pinfunction "S8_9") (pintype "passive"))
      (node (ref "J6") (pin "1") (pinfunction "S1_1") (pintype "passive"))
      (node (ref "J6") (pin "2") (pinfunction "S2_2") (pintype "passive"))
      (node (ref "J6") (pin "3") (pinfunction "S3_3") (pintype "passive"))
      (node (ref "J6") (pin "4") (pinfunction "S4_4") (pintype "passive"))
      (node (ref "J6") (pin "5") (pinfunction "S_5") (pintype "passive"))
      (node (ref "J6") (pin "6") (pinfunction "S5_6") (pintype "passive"))
      (node (ref "J6") (pin "7") (pinfunction "S6_7") (pintype "passive"))
      (node (ref "J6") (pin "8") (pinfunction "S7_8") (pintype "passive"))
      (node (ref "J6") (pin "9") (pinfunction "S8_9") (pintype "passive"))
      (node (ref "J8") (pin "1") (pinfunction "1_1") (pintype "passive"))
      (node (ref "PAD1") (pin "1") (pinfunction "P_1") (pintype "passive"))
      (node (ref "PAD2") (pin "1") (pinfunction "P_1") (pintype "passive"))
      (node (ref "PAD3") (pin "1") (pinfunction "P_1") (pintype "passive"))
      (node (ref "PAD4") (pin "1") (pinfunction "P_1") (pintype "passive"))
      (node (ref "PAD5") (pin "1") (pinfunction "P_1") (pintype "passive"))
      (node (ref "PAD6") (pin "1") (pinfunction "P_1") (pintype "passive"))
      (node (ref "R10") (pin "2") (pinfunction "2_2") (pintype "passive"))
      (node (ref "R13") (pin "2") (pinfunction "2_2") (pintype "passive"))
      (node (ref "R4") (pin "2") (pinfunction "2_2") (pintype "passive"))
      (node (ref "R45") (pin "2") (pinfunction "2_2") (pintype "passive"))
      (node (ref "R46") (pin "2") (pinfunction "2_2") (pintype "passive"))
      (node (ref "R47") (pin "2") (pinfunction "2_2") (pintype "passive"))
      (node (ref "R48") (pin "2") (pinfunction "2_2") (pintype "passive"))
      (node (ref "R5") (pin "2") (pinfunction "2_2") (pintype "passive"))
      (node (ref "R53") (pin "2") (pinfunction "2_2") (pintype "passive"))
      (node (ref "R54") (pin "2") (pinfunction "2_2") (pintype "passive"))
      (node (ref "R55") (pin "2") (pinfunction "2_2") (pintype "passive"))
      (node (ref "R56") (pin "2") (pinfunction "2_2") (pintype "passive"))
      (node (ref "R57") (pin "2") (pinfunction "2_2") (pintype "passive"))
      (node (ref "R58") (pin "2") (pinfunction "2_2") (pintype "passive"))
      (node (ref "R59") (pin "2") (pinfunction "2_2") (pintype "passive"))
      (node (ref "R60") (pin "2") (pinfunction "2_2") (pintype "passive"))
      (node (ref "R8") (pin "2") (pinfunction "2_2") (pintype "passive"))
    )
    (net (code "23") (name "IN1") (class "Default")
      (node (ref "J1") (pin "8") (pinfunction "S7_8") (pintype "passive"))
      (node (ref "J4") (pin "8") (pinfunction "S7_8") (pintype "passive"))
    )
    (net (code "24") (name "IN2") (class "Default")
      (node (ref "J1") (pin "7") (pinfunction "S6_7") (pintype "passive"))
      (node (ref "J4") (pin "7") (pinfunction "S6_7") (pintype "passive"))
    )
    (net (code "25") (name "IN3") (class "Default")
      (node (ref "J1") (pin "6") (pinfunction "S5_6") (pintype "passive"))
      (node (ref "J4") (pin "6") (pinfunction "S5_6") (pintype "passive"))
    )
    (net (code "26") (name "IN4") (class "Default")
      (node (ref "J1") (pin "4") (pinfunction "S4_4") (pintype "passive"))
      (node (ref "J4") (pin "4") (pinfunction "S4_4") (pintype "passive"))
    )
    (net (code "27") (name "IN5") (class "Default")
      (node (ref "J2") (pin "8") (pinfunction "S7_8") (pintype "passive"))
      (node (ref "J5") (pin "8") (pinfunction "S7_8") (pintype "passive"))
    )
    (net (code "28") (name "IN6") (class "Default")
      (node (ref "J2") (pin "7") (pinfunction "S6_7") (pintype "passive"))
      (node (ref "J5") (pin "7") (pinfunction "S6_7") (pintype "passive"))
    )
    (net (code "29") (name "IN7") (class "Default")
      (node (ref "J2") (pin "6") (pinfunction "S5_6") (pintype "passive"))
      (node (ref "J5") (pin "6") (pinfunction "S5_6") (pintype "passive"))
    )
    (net (code "30") (name "IN8") (class "Default")
      (node (ref "J2") (pin "4") (pinfunction "S4_4") (pintype "passive"))
      (node (ref "J5") (pin "4") (pinfunction "S4_4") (pintype "passive"))
    )
    (net (code "31") (name "Net-(D1-PadA)") (class "Default")
      (node (ref "D1") (pin "A") (pinfunction "A_A") (pintype "passive"))
      (node (ref "J25") (pin "10") (pinfunction "12V_10") (pintype "power_in"))
      (node (ref "J25") (pin "9") (pinfunction "12V_9") (pintype "power_in"))
    )
    (net (code "32") (name "Net-(D2-PadC)") (class "Default")
      (node (ref "D2") (pin "C") (pinfunction "C_C") (pintype "passive"))
      (node (ref "J25") (pin "1") (pinfunction "-12V_1") (pintype "power_in"))
      (node (ref "J25") (pin "2") (pinfunction "-12V_2") (pintype "power_in"))
    )
    (net (code "33") (name "Net-(IC1A--IN)") (class "Default")
      (node (ref "IC1") (pin "1") (pinfunction "OUT_1") (pintype "output"))
      (node (ref "IC1") (pin "2") (pinfunction "-IN_2") (pintype "input"))
      (node (ref "J20") (pin "3") (pinfunction "1_3") (pintype "passive"))
      (node (ref "R6") (pin "2") (pinfunction "2_2") (pintype "passive"))
    )
    (net (code "34") (name "Net-(IC1B--IN)") (class "Default")
      (node (ref "IC1") (pin "6") (pinfunction "-IN_6") (pintype "input"))
      (node (ref "IC1") (pin "7") (pinfunction "OUT_7") (pintype "output"))
      (node (ref "J15") (pin "3") (pinfunction "1_3") (pintype "passive"))
      (node (ref "R11") (pin "2") (pinfunction "2_2") (pintype "passive"))
    )
    (net (code "35") (name "Net-(IC1C--IN)") (class "Default")
      (node (ref "IC1") (pin "8") (pinfunction "OUT_8") (pintype "output"))
      (node (ref "IC1") (pin "9") (pinfunction "-IN_9") (pintype "input"))
      (node (ref "J8") (pin "3") (pinfunction "1_3") (pintype "passive"))
      (node (ref "R16") (pin "2") (pinfunction "2_2") (pintype "passive"))
    )
    (net (code "36") (name "Net-(IC1D--IN)") (class "Default")
      (node (ref "IC1") (pin "13") (pinfunction "-IN_13") (pintype "input"))
      (node (ref "IC1") (pin "14") (pinfunction "OUT_14") (pintype "output"))
      (node (ref "J16") (pin "3") (pinfunction "1_3") (pintype "passive"))
      (node (ref "R25") (pin "2") (pinfunction "2_2") (pintype "passive"))
    )
    (net (code "37") (name "Net-(IC2A-+IN)") (class "Default")
      (node (ref "IC2") (pin "3") (pinfunction "+IN_3") (pintype "input"))
      (node (ref "J20") (pin "2") (pinfunction "1_2") (pintype "passive"))
    )
    (net (code "38") (name "Net-(IC2A--IN)") (class "Default")
      (node (ref "IC2") (pin "2") (pinfunction "-IN_2") (pintype "input"))
      (node (ref "R6") (pin "1") (pinfunction "1_1") (pintype "passive"))
      (node (ref "R7") (pin "2") (pinfunction "2_2") (pintype "passive"))
      (node (ref "R9") (pin "1") (pinfunction "1_1") (pintype "passive"))
    )
    (net (code "39") (name "Net-(IC2B--IN)") (class "Default")
      (node (ref "IC2") (pin "6") (pinfunction "-IN_6") (pintype "input"))
      (node (ref "LED1") (pin "A") (pinfunction "A_A") (pintype "passive"))
      (node (ref "R5") (pin "1") (pinfunction "1_1") (pintype "passive"))
    )
    (net (code "40") (name "Net-(IC2B-OUT)") (class "Default")
      (node (ref "IC2") (pin "7") (pinfunction "OUT_7") (pintype "output"))
      (node (ref "LED1") (pin "K") (pinfunction "C_K") (pintype "passive"))
    )
    (net (code "41") (name "Net-(IC2C--IN)") (class "Default")
      (node (ref "IC2") (pin "9") (pinfunction "-IN_9") (pintype "input"))
      (node (ref "LED2") (pin "A") (pinfunction "A_A") (pintype "passive"))
      (node (ref "R8") (pin "1") (pinfunction "1_1") (pintype "passive"))
    )
    (net (code "42") (name "Net-(IC2C-OUT)") (class "Default")
      (node (ref "IC2") (pin "8") (pinfunction "OUT_8") (pintype "output"))
      (node (ref "LED2") (pin "K") (pinfunction "C_K") (pintype "passive"))
    )
    (net (code "43") (name "Net-(IC2D-+IN)") (class "Default")
      (node (ref "IC2") (pin "12") (pinfunction "+IN_12") (pintype "input"))
      (node (ref "J15") (pin "2") (pinfunction "1_2") (pintype "passive"))
    )
    (net (code "44") (name "Net-(IC2D--IN)") (class "Default")
      (node (ref "IC2") (pin "13") (pinfunction "-IN_13") (pintype "input"))
      (node (ref "R11") (pin "1") (pinfunction "1_1") (pintype "passive"))
      (node (ref "R12") (pin "2") (pinfunction "2_2") (pintype "passive"))
      (node (ref "R14") (pin "1") (pinfunction "1_1") (pintype "passive"))
    )
    (net (code "45") (name "Net-(IC3A-+IN)") (class "Default")
      (node (ref "IC3") (pin "3") (pinfunction "+IN_3") (pintype "input"))
      (node (ref "J8") (pin "2") (pinfunction "1_2") (pintype "passive"))
    )
    (net (code "46") (name "Net-(IC3A--IN)") (class "Default")
      (node (ref "IC3") (pin "2") (pinfunction "-IN_2") (pintype "input"))
      (node (ref "R16") (pin "1") (pinfunction "1_1") (pintype "passive"))
      (node (ref "R17") (pin "2") (pinfunction "2_2") (pintype "passive"))
      (node (ref "R19") (pin "1") (pinfunction "1_1") (pintype "passive"))
    )
    (net (code "47") (name "Net-(IC3B--IN)") (class "Default")
      (node (ref "IC3") (pin "6") (pinfunction "-IN_6") (pintype "input"))
      (node (ref "LED3") (pin "A") (pinfunction "A_A") (pintype "passive"))
      (node (ref "R10") (pin "1") (pinfunction "1_1") (pintype "passive"))
    )
    (net (code "48") (name "Net-(IC3B-OUT)") (class "Default")
      (node (ref "IC3") (pin "7") (pinfunction "OUT_7") (pintype "output"))
      (node (ref "LED3") (pin "K") (pinfunction "C_K") (pintype "passive"))
    )
    (net (code "49") (name "Net-(IC3C--IN)") (class "Default")
      (node (ref "IC3") (pin "9") (pinfunction "-IN_9") (pintype "input"))
      (node (ref "LED4") (pin "A") (pinfunction "A_A") (pintype "passive"))
      (node (ref "R13") (pin "1") (pinfunction "1_1") (pintype "passive"))
    )
    (net (code "50") (name "Net-(IC3C-OUT)") (class "Default")
      (node (ref "IC3") (pin "8") (pinfunction "OUT_8") (pintype "output"))
      (node (ref "LED4") (pin "K") (pinfunction "C_K") (pintype "passive"))
    )
    (net (code "51") (name "Net-(IC3D-+IN)") (class "Default")
      (node (ref "IC3") (pin "12") (pinfunction "+IN_12") (pintype "input"))
      (node (ref "J16") (pin "2") (pinfunction "1_2") (pintype "passive"))
    )
    (net (code "52") (name "Net-(IC3D--IN)") (class "Default")
      (node (ref "IC3") (pin "13") (pinfunction "-IN_13") (pintype "input"))
      (node (ref "R24") (pin "1") (pinfunction "1_1") (pintype "passive"))
      (node (ref "R25") (pin "1") (pinfunction "1_1") (pintype "passive"))
      (node (ref "R26") (pin "2") (pinfunction "2_2") (pintype "passive"))
    )
    (net (code "53") (name "Net-(IC5A--IN)") (class "Default")
      (node (ref "IC5") (pin "1") (pinfunction "OUT_1") (pintype "output"))
      (node (ref "IC5") (pin "2") (pinfunction "-IN_2") (pintype "input"))
      (node (ref "J21") (pin "3") (pinfunction "1_3") (pintype "passive"))
      (node (ref "R15") (pin "2") (pinfunction "2_2") (pintype "passive"))
    )
    (net (code "54") (name "Net-(IC5B--IN)") (class "Default")
      (node (ref "IC5") (pin "6") (pinfunction "-IN_6") (pintype "input"))
      (node (ref "IC5") (pin "7") (pinfunction "OUT_7") (pintype "output"))
      (node (ref "J22") (pin "3") (pinfunction "1_3") (pintype "passive"))
      (node (ref "R27") (pin "2") (pinfunction "2_2") (pintype "passive"))
    )
    (net (code "55") (name "Net-(IC5C--IN)") (class "Default")
      (node (ref "IC5") (pin "8") (pinfunction "OUT_8") (pintype "output"))
      (node (ref "IC5") (pin "9") (pinfunction "-IN_9") (pintype "input"))
      (node (ref "J24") (pin "3") (pinfunction "1_3") (pintype "passive"))
      (node (ref "R39") (pin "2") (pinfunction "2_2") (pintype "passive"))
    )
    (net (code "56") (name "Net-(IC5D--IN)") (class "Default")
      (node (ref "IC5") (pin "13") (pinfunction "-IN_13") (pintype "input"))
      (node (ref "IC5") (pin "14") (pinfunction "OUT_14") (pintype "output"))
      (node (ref "J23") (pin "4") (pinfunction "1_4") (pintype "passive"))
      (node (ref "R34") (pin "2") (pinfunction "2_2") (pintype "passive"))
    )
    (net (code "57") (name "Net-(IC6A--IN)") (class "Default")
      (node (ref "IC6") (pin "2") (pinfunction "-IN_2") (pintype "input"))
      (node (ref "LED5") (pin "A") (pinfunction "A_A") (pintype "passive"))
      (node (ref "R45") (pin "1") (pinfunction "1_1") (pintype "passive"))
    )
    (net (code "58") (name "Net-(IC6A-OUT)") (class "Default")
      (node (ref "IC6") (pin "1") (pinfunction "OUT_1") (pintype "output"))
      (node (ref "LED5") (pin "K") (pinfunction "C_K") (pintype "passive"))
    )
    (net (code "59") (name "Net-(IC6B-+IN)") (class "Default")
      (node (ref "IC6") (pin "5") (pinfunction "+IN_5") (pintype "input"))
      (node (ref "J21") (pin "2") (pinfunction "1_2") (pintype "passive"))
    )
    (net (code "60") (name "Net-(IC6B--IN)") (class "Default")
      (node (ref "IC6") (pin "6") (pinfunction "-IN_6") (pintype "input"))
      (node (ref "R15") (pin "1") (pinfunction "1_1") (pintype "passive"))
      (node (ref "R18") (pin "2") (pinfunction "2_2") (pintype "passive"))
      (node (ref "R20") (pin "1") (pinfunction "1_1") (pintype "passive"))
    )
    (net (code "61") (name "Net-(IC7A--IN)") (class "Default")
      (node (ref "IC7") (pin "2") (pinfunction "-IN_2") (pintype "input"))
      (node (ref "LED6") (pin "A") (pinfunction "A_A") (pintype "passive"))
      (node (ref "R46") (pin "1") (pinfunction "1_1") (pintype "passive"))
    )
    (net (code "62") (name "Net-(IC7A-OUT)") (class "Default")
      (node (ref "IC7") (pin "1") (pinfunction "OUT_1") (pintype "output"))
      (node (ref "LED6") (pin "K") (pinfunction "C_K") (pintype "passive"))
    )
    (net (code "63") (name "Net-(IC7B-+IN)") (class "Default")
      (node (ref "IC7") (pin "5") (pinfunction "+IN_5") (pintype "input"))
      (node (ref "JP1") (pin "2") (pinfunction "2_2") (pintype "passive"))
      (node (ref "JP1") (pin "4") (pinfunction "4_4") (pintype "passive"))
      (node (ref "JP1") (pin "6") (pinfunction "6_6") (pintype "passive"))
    )
    (net (code "64") (name "Net-(IC7B--IN)") (class "Default")
      (node (ref "IC7") (pin "6") (pinfunction "-IN_6") (pintype "input"))
      (node (ref "IC7") (pin "7") (pinfunction "OUT_7") (pintype "output"))
      (node (ref "J27") (pin "7") (pinfunction "1_7") (pintype "passive"))
      (node (ref "J27") (pin "8") (pinfunction "1_8") (pintype "passive"))
    )
    (net (code "65") (name "Net-(IC7C-+IN)") (class "Default")
      (node (ref "IC7") (pin "10") (pinfunction "+IN_10") (pintype "input"))
      (node (ref "JP2") (pin "2") (pinfunction "2_2") (pintype "passive"))
      (node (ref "JP2") (pin "4") (pinfunction "4_4") (pintype "passive"))
      (node (ref "JP2") (pin "6") (pinfunction "6_6") (pintype "passive"))
    )
    (net (code "66") (name "Net-(IC7C--IN)") (class "Default")
      (node (ref "IC7") (pin "8") (pinfunction "OUT_8") (pintype "output"))
      (node (ref "IC7") (pin "9") (pinfunction "-IN_9") (pintype "input"))
      (node (ref "J27") (pin "3") (pinfunction "1_3") (pintype "passive"))
      (node (ref "J27") (pin "4") (pinfunction "1_4") (pintype "passive"))
    )
    (net (code "67") (name "Net-(IC7D-+IN)") (class "Default")
      (node (ref "IC7") (pin "12") (pinfunction "+IN_12") (pintype "input"))
      (node (ref "J22") (pin "2") (pinfunction "1_2") (pintype "passive"))
    )
    (net (code "68") (name "Net-(IC7D--IN)") (class "Default")
      (node (ref "IC7") (pin "13") (pinfunction "-IN_13") (pintype "input"))
      (node (ref "R27") (pin "1") (pinfunction "1_1") (pintype "passive"))
      (node (ref "R28") (pin "2") (pinfunction "2_2") (pintype "passive"))
      (node (ref "R30") (pin "1") (pinfunction "1_1") (pintype "passive"))
    )
    (net (code "69") (name "Net-(IC8A-+IN)") (class "Default")
      (node (ref "IC8") (pin "3") (pinfunction "+IN_3") (pintype "input"))
      (node (ref "J23") (pin "2") (pinfunction "1_2") (pintype "passive"))
    )
    (net (code "70") (name "Net-(IC8A--IN)") (class "Default")
      (node (ref "IC8") (pin "2") (pinfunction "-IN_2") (pintype "input"))
      (node (ref "R34") (pin "1") (pinfunction "1_1") (pintype "passive"))
      (node (ref "R35") (pin "2") (pinfunction "2_2") (pintype "passive"))
      (node (ref "R37") (pin "1") (pinfunction "1_1") (pintype "passive"))
    )
    (net (code "71") (name "Net-(IC8B--IN)") (class "Default")
      (node (ref "IC8") (pin "6") (pinfunction "-IN_6") (pintype "input"))
      (node (ref "LED7") (pin "A") (pinfunction "A_A") (pintype "passive"))
      (node (ref "R47") (pin "1") (pinfunction "1_1") (pintype "passive"))
    )
    (net (code "72") (name "Net-(IC8B-OUT)") (class "Default")
      (node (ref "IC8") (pin "7") (pinfunction "OUT_7") (pintype "output"))
      (node (ref "LED7") (pin "K") (pinfunction "C_K") (pintype "passive"))
    )
    (net (code "73") (name "Net-(IC8C--IN)") (class "Default")
      (node (ref "IC8") (pin "9") (pinfunction "-IN_9") (pintype "input"))
      (node (ref "LED8") (pin "A") (pinfunction "A_A") (pintype "passive"))
      (node (ref "R48") (pin "1") (pinfunction "1_1") (pintype "passive"))
    )
    (net (code "74") (name "Net-(IC8C-OUT)") (class "Default")
      (node (ref "IC8") (pin "8") (pinfunction "OUT_8") (pintype "output"))
      (node (ref "LED8") (pin "K") (pinfunction "C_K") (pintype "passive"))
    )
    (net (code "75") (name "Net-(IC8D-+IN)") (class "Default")
      (node (ref "IC8") (pin "12") (pinfunction "+IN_12") (pintype "input"))
      (node (ref "J24") (pin "2") (pinfunction "1_2") (pintype "passive"))
    )
    (net (code "76") (name "Net-(IC8D--IN)") (class "Default")
      (node (ref "IC8") (pin "13") (pinfunction "-IN_13") (pintype "input"))
      (node (ref "R39") (pin "1") (pinfunction "1_1") (pintype "passive"))
      (node (ref "R40") (pin "2") (pinfunction "2_2") (pintype "passive"))
      (node (ref "R44") (pin "1") (pinfunction "1_1") (pintype "passive"))
    )
    (net (code "77") (name "Net-(J7-Pad1)") (class "Default")
      (node (ref "J7") (pin "1") (pinfunction "1_1") (pintype "passive"))
      (node (ref "P3BIAS") (pin "1") (pinfunction "1_1") (pintype "passive"))
      (node (ref "P3CV") (pin "1") (pinfunction "1_1") (pintype "passive"))
      (node (ref "R32") (pin "1") (pinfunction "1_1") (pintype "passive"))
    )
    (net (code "78") (name "Net-(J7B-1)") (class "Default")
      (node (ref "J7") (pin "2") (pinfunction "1_2") (pintype "passive"))
      (node (ref "R31") (pin "2") (pinfunction "2_2") (pintype "passive"))
      (node (ref "R32") (pin "2") (pinfunction "2_2") (pintype "passive"))
    )
    (net (code "79") (name "Net-(J7C-1)") (class "Default")
      (node (ref "J7") (pin "3") (pinfunction "1_3") (pintype "passive"))
      (node (ref "P3CV") (pin "3") (pinfunction "3_3") (pintype "passive"))
    )
    (net (code "80") (name "Net-(J7D-1)") (class "Default")
      (node (ref "J7") (pin "4") (pinfunction "1_4") (pintype "passive"))
      (node (ref "P3BIAS") (pin "2") (pinfunction "2_2") (pintype "passive"))
    )
    (net (code "81") (name "Net-(J8D-1)") (class "Default")
      (node (ref "J8") (pin "4") (pinfunction "1_4") (pintype "passive"))
      (node (ref "R19") (pin "2") (pinfunction "2_2") (pintype "passive"))
    )
    (net (code "82") (name "Net-(J9-Pad1)") (class "Default")
      (node (ref "J9") (pin "1") (pinfunction "1_1") (pintype "passive"))
      (node (ref "P1BIAS") (pin "1") (pinfunction "1_1") (pintype "passive"))
      (node (ref "P1CV") (pin "1") (pinfunction "1_1") (pintype "passive"))
      (node (ref "R22") (pin "1") (pinfunction "1_1") (pintype "passive"))
    )
    (net (code "83") (name "Net-(J9B-1)") (class "Default")
      (node (ref "J9") (pin "2") (pinfunction "1_2") (pintype "passive"))
      (node (ref "R21") (pin "2") (pinfunction "2_2") (pintype "passive"))
      (node (ref "R22") (pin "2") (pinfunction "2_2") (pintype "passive"))
    )
    (net (code "84") (name "Net-(J9C-1)") (class "Default")
      (node (ref "J9") (pin "3") (pinfunction "1_3") (pintype "passive"))
      (node (ref "P1CV") (pin "3") (pinfunction "3_3") (pintype "passive"))
    )
    (net (code "85") (name "Net-(J9D-1)") (class "Default")
      (node (ref "J9") (pin "4") (pinfunction "1_4") (pintype "passive"))
      (node (ref "P1BIAS") (pin "2") (pinfunction "2_2") (pintype "passive"))
    )
    (net (code "86") (name "Net-(J10-Pad1)") (class "Default")
      (node (ref "J10") (pin "1") (pinfunction "1_1") (pintype "passive"))
      (node (ref "P2BIAS") (pin "1") (pinfunction "1_1") (pintype "passive"))
      (node (ref "P2CV") (pin "1") (pinfunction "1_1") (pintype "passive"))
      (node (ref "R29") (pin "1") (pinfunction "1_1") (pintype "passive"))
    )
    (net (code "87") (name "Net-(J10B-1)") (class "Default")
      (node (ref "J10") (pin "2") (pinfunction "1_2") (pintype "passive"))
      (node (ref "R23") (pin "2") (pinfunction "2_2") (pintype "passive"))
      (node (ref "R29") (pin "2") (pinfunction "2_2") (pintype "passive"))
    )
    (net (code "88") (name "Net-(J10C-1)") (class "Default")
      (node (ref "J10") (pin "3") (pinfunction "1_3") (pintype "passive"))
      (node (ref "P2CV") (pin "3") (pinfunction "3_3") (pintype "passive"))
    )
    (net (code "89") (name "Net-(J10D-1)") (class "Default")
      (node (ref "J10") (pin "4") (pinfunction "1_4") (pintype "passive"))
      (node (ref "P2BIAS") (pin "2") (pinfunction "2_2") (pintype "passive"))
    )
    (net (code "90") (name "Net-(J11-Pad1)") (class "Default")
      (node (ref "J11") (pin "1") (pinfunction "1_1") (pintype "passive"))
      (node (ref "P4BIAS") (pin "1") (pinfunction "1_1") (pintype "passive"))
      (node (ref "P4CV") (pin "1") (pinfunction "1_1") (pintype "passive"))
      (node (ref "R36") (pin "1") (pinfunction "1_1") (pintype "passive"))
    )
    (net (code "91") (name "Net-(J11B-1)") (class "Default")
      (node (ref "J11") (pin "2") (pinfunction "1_2") (pintype "passive"))
      (node (ref "R33") (pin "2") (pinfunction "2_2") (pintype "passive"))
      (node (ref "R36") (pin "2") (pinfunction "2_2") (pintype "passive"))
    )
    (net (code "92") (name "Net-(J11C-1)") (class "Default")
      (node (ref "J11") (pin "3") (pinfunction "1_3") (pintype "passive"))
      (node (ref "P4CV") (pin "3") (pinfunction "3_3") (pintype "passive"))
    )
    (net (code "93") (name "Net-(J11D-1)") (class "Default")
      (node (ref "J11") (pin "4") (pinfunction "1_4") (pintype "passive"))
      (node (ref "P4BIAS") (pin "2") (pinfunction "2_2") (pintype "passive"))
    )
    (net (code "94") (name "Net-(J12-Pad1)") (class "Default")
      (node (ref "J12") (pin "1") (pinfunction "1_1") (pintype "passive"))
      (node (ref "P5BIAS") (pin "1") (pinfunction "1_1") (pintype "passive"))
      (node (ref "P5CV") (pin "1") (pinfunction "1_1") (pintype "passive"))
      (node (ref "R41") (pin "1") (pinfunction "1_1") (pintype "passive"))
    )
    (net (code "95") (name "Net-(J12B-1)") (class "Default")
      (node (ref "J12") (pin "2") (pinfunction "1_2") (pintype "passive"))
      (node (ref "R38") (pin "2") (pinfunction "2_2") (pintype "passive"))
      (node (ref "R41") (pin "2") (pinfunction "2_2") (pintype "passive"))
    )
    (net (code "96") (name "Net-(J12C-1)") (class "Default")
      (node (ref "J12") (pin "3") (pinfunction "1_3") (pintype "passive"))
      (node (ref "P5CV") (pin "3") (pinfunction "3_3") (pintype "passive"))
    )
    (net (code "97") (name "Net-(J12D-1)") (class "Default")
      (node (ref "J12") (pin "4") (pinfunction "1_4") (pintype "passive"))
      (node (ref "P5BIAS") (pin "2") (pinfunction "2_2") (pintype "passive"))
    )
    (net (code "98") (name "Net-(J15D-1)") (class "Default")
      (node (ref "J15") (pin "4") (pinfunction "1_4") (pintype "passive"))
      (node (ref "R14") (pin "2") (pinfunction "2_2") (pintype "passive"))
    )
    (net (code "99") (name "Net-(J16D-1)") (class "Default")
      (node (ref "J16") (pin "4") (pinfunction "1_4") (pintype "passive"))
      (node (ref "R24") (pin "2") (pinfunction "2_2") (pintype "passive"))
    )
    (net (code "100") (name "Net-(J17-Pad1)") (class "Default")
      (node (ref "J17") (pin "1") (pinfunction "1_1") (pintype "passive"))
      (node (ref "P6BIAS") (pin "1") (pinfunction "1_1") (pintype "passive"))
      (node (ref "P6CV") (pin "1") (pinfunction "1_1") (pintype "passive"))
      (node (ref "R42") (pin "1") (pinfunction "1_1") (pintype "passive"))
    )
    (net (code "101") (name "Net-(J17B-1)") (class "Default")
      (node (ref "J17") (pin "2") (pinfunction "1_2") (pintype "passive"))
      (node (ref "R42") (pin "2") (pinfunction "2_2") (pintype "passive"))
      (node (ref "R43") (pin "2") (pinfunction "2_2") (pintype "passive"))
    )
    (net (code "102") (name "Net-(J17C-1)") (class "Default")
      (node (ref "J17") (pin "3") (pinfunction "1_3") (pintype "passive"))
      (node (ref "P6CV") (pin "3") (pinfunction "3_3") (pintype "passive"))
    )
    (net (code "103") (name "Net-(J17D-1)") (class "Default")
      (node (ref "J17") (pin "4") (pinfunction "1_4") (pintype "passive"))
      (node (ref "P6BIAS") (pin "2") (pinfunction "2_2") (pintype "passive"))
    )
    (net (code "104") (name "Net-(J18-Pad1)") (class "Default")
      (node (ref "J18") (pin "1") (pinfunction "1_1") (pintype "passive"))
      (node (ref "P7BIAS") (pin "1") (pinfunction "1_1") (pintype "passive"))
      (node (ref "P7CV") (pin "1") (pinfunction "1_1") (pintype "passive"))
      (node (ref "R50") (pin "1") (pinfunction "1_1") (pintype "passive"))
    )
    (net (code "105") (name "Net-(J18B-1)") (class "Default")
      (node (ref "J18") (pin "2") (pinfunction "1_2") (pintype "passive"))
      (node (ref "R49") (pin "2") (pinfunction "2_2") (pintype "passive"))
      (node (ref "R50") (pin "2") (pinfunction "2_2") (pintype "passive"))
    )
    (net (code "106") (name "Net-(J18C-1)") (class "Default")
      (node (ref "J18") (pin "3") (pinfunction "1_3") (pintype "passive"))
      (node (ref "P7BIAS") (pin "2") (pinfunction "2_2") (pintype "passive"))
    )
    (net (code "107") (name "Net-(J18D-1)") (class "Default")
      (node (ref "J18") (pin "4") (pinfunction "1_4") (pintype "passive"))
      (node (ref "P7CV") (pin "3") (pinfunction "3_3") (pintype "passive"))
    )
    (net (code "108") (name "Net-(J19-Pad1)") (class "Default")
      (node (ref "J19") (pin "1") (pinfunction "1_1") (pintype "passive"))
      (node (ref "P8BIAS") (pin "1") (pinfunction "1_1") (pintype "passive"))
      (node (ref "P8CV") (pin "1") (pinfunction "1_1") (pintype "passive"))
      (node (ref "R52") (pin "1") (pinfunction "1_1") (pintype "passive"))
    )
    (net (code "109") (name "Net-(J19B-1)") (class "Default")
      (node (ref "J19") (pin "2") (pinfunction "1_2") (pintype "passive"))
      (node (ref "R51") (pin "2") (pinfunction "2_2") (pintype "passive"))
      (node (ref "R52") (pin "2") (pinfunction "2_2") (pintype "passive"))
    )
    (net (code "110") (name "Net-(J19C-1)") (class "Default")
      (node (ref "J19") (pin "3") (pinfunction "1_3") (pintype "passive"))
      (node (ref "P8CV") (pin "3") (pinfunction "3_3") (pintype "passive"))
    )
    (net (code "111") (name "Net-(J19D-1)") (class "Default")
      (node (ref "J19") (pin "4") (pinfunction "1_4") (pintype "passive"))
      (node (ref "P8BIAS") (pin "2") (pinfunction "2_2") (pintype "passive"))
    )
    (net (code "112") (name "Net-(J20D-1)") (class "Default")
      (node (ref "J20") (pin "4") (pinfunction "1_4") (pintype "passive"))
      (node (ref "R9") (pin "2") (pinfunction "2_2") (pintype "passive"))
    )
    (net (code "113") (name "Net-(J21D-1)") (class "Default")
      (node (ref "J21") (pin "4") (pinfunction "1_4") (pintype "passive"))
      (node (ref "R20") (pin "2") (pinfunction "2_2") (pintype "passive"))
    )
    (net (code "114") (name "Net-(J22D-1)") (class "Default")
      (node (ref "J22") (pin "4") (pinfunction "1_4") (pintype "passive"))
      (node (ref "R30") (pin "2") (pinfunction "2_2") (pintype "passive"))
    )
    (net (code "115") (name "Net-(J23C-1)") (class "Default")
      (node (ref "J23") (pin "3") (pinfunction "1_3") (pintype "passive"))
      (node (ref "R37") (pin "2") (pinfunction "2_2") (pintype "passive"))
    )
    (net (code "116") (name "Net-(J24D-1)") (class "Default")
      (node (ref "J24") (pin "4") (pinfunction "1_4") (pintype "passive"))
      (node (ref "R44") (pin "2") (pinfunction "2_2") (pintype "passive"))
    )
    (net (code "117") (name "Net-(P1CV-Pad2)") (class "Default")
      (node (ref "P1CV") (pin "2") (pinfunction "2_2") (pintype "passive"))
      (node (ref "R21") (pin "1") (pinfunction "1_1") (pintype "passive"))
    )
    (net (code "118") (name "Net-(P2CV-Pad2)") (class "Default")
      (node (ref "P2CV") (pin "2") (pinfunction "2_2") (pintype "passive"))
      (node (ref "R23") (pin "1") (pinfunction "1_1") (pintype "passive"))
    )
    (net (code "119") (name "Net-(P3CV-Pad2)") (class "Default")
      (node (ref "P3CV") (pin "2") (pinfunction "2_2") (pintype "passive"))
      (node (ref "R31") (pin "1") (pinfunction "1_1") (pintype "passive"))
    )
    (net (code "120") (name "Net-(P4CV-Pad2)") (class "Default")
      (node (ref "P4CV") (pin "2") (pinfunction "2_2") (pintype "passive"))
      (node (ref "R33") (pin "1") (pinfunction "1_1") (pintype "passive"))
    )
    (net (code "121") (name "Net-(P5CV-Pad2)") (class "Default")
      (node (ref "P5CV") (pin "2") (pinfunction "2_2") (pintype "passive"))
      (node (ref "R38") (pin "1") (pinfunction "1_1") (pintype "passive"))
    )
    (net (code "122") (name "Net-(P6CV-Pad2)") (class "Default")
      (node (ref "P6CV") (pin "2") (pinfunction "2_2") (pintype "passive"))
      (node (ref "R43") (pin "1") (pinfunction "1_1") (pintype "passive"))
    )
    (net (code "123") (name "Net-(P7CV-Pad2)") (class "Default")
      (node (ref "P7CV") (pin "2") (pinfunction "2_2") (pintype "passive"))
      (node (ref "R49") (pin "1") (pinfunction "1_1") (pintype "passive"))
    )
    (net (code "124") (name "Net-(P8CV-Pad2)") (class "Default")
      (node (ref "P8CV") (pin "2") (pinfunction "2_2") (pintype "passive"))
      (node (ref "R51") (pin "1") (pinfunction "1_1") (pintype "passive"))
    )
    (net (code "125") (name "OUT1") (class "Default")
      (node (ref "J1") (pin "3") (pinfunction "S3_3") (pintype "passive"))
      (node (ref "J4") (pin "3") (pinfunction "S3_3") (pintype "passive"))
    )
    (net (code "126") (name "OUT2") (class "Default")
      (node (ref "J1") (pin "2") (pinfunction "S2_2") (pintype "passive"))
      (node (ref "J4") (pin "2") (pinfunction "S2_2") (pintype "passive"))
    )
    (net (code "127") (name "OUT3") (class "Default")
      (node (ref "J1") (pin "1") (pinfunction "S1_1") (pintype "passive"))
      (node (ref "J4") (pin "1") (pinfunction "S1_1") (pintype "passive"))
    )
    (net (code "128") (name "OUT4") (class "Default")
      (node (ref "J1") (pin "5") (pinfunction "S_5") (pintype "passive"))
      (node (ref "J4") (pin "5") (pinfunction "S_5") (pintype "passive"))
    )
    (net (code "129") (name "OUT5") (class "Default")
      (node (ref "J2") (pin "3") (pinfunction "S3_3") (pintype "passive"))
      (node (ref "J5") (pin "3") (pinfunction "S3_3") (pintype "passive"))
    )
    (net (code "130") (name "OUT6") (class "Default")
      (node (ref "J2") (pin "2") (pinfunction "S2_2") (pintype "passive"))
      (node (ref "J5") (pin "2") (pinfunction "S2_2") (pintype "passive"))
    )
    (net (code "131") (name "OUT7") (class "Default")
      (node (ref "J2") (pin "1") (pinfunction "S1_1") (pintype "passive"))
      (node (ref "J5") (pin "1") (pinfunction "S1_1") (pintype "passive"))
    )
    (net (code "132") (name "OUT8") (class "Default")
      (node (ref "J2") (pin "5") (pinfunction "S_5") (pintype "passive"))
      (node (ref "J5") (pin "5") (pinfunction "S_5") (pintype "passive"))
    )
    (net (code "133") (name "SUM1-4") (class "Default")
      (node (ref "J3") (pin "12") (pinfunction "S11_12") (pintype "passive"))
      (node (ref "J6") (pin "12") (pinfunction "S11_12") (pintype "passive"))
    )
    (net (code "134") (name "SUM1-8") (class "Default")
      (node (ref "J3") (pin "11") (pinfunction "S10_11") (pintype "passive"))
      (node (ref "J6") (pin "11") (pinfunction "S10_11") (pintype "passive"))
    )
    (net (code "135") (name "SUM5-8") (class "Default")
      (node (ref "J3") (pin "10") (pinfunction "S9_10") (pintype "passive"))
      (node (ref "J6") (pin "10") (pinfunction "S9_10") (pintype "passive"))
    )
    (net (code "136") (name "VREF1-4") (class "Default")
      (node (ref "J29") (pin "7") (pinfunction "1_7") (pintype "passive"))
      (node (ref "J29") (pin "8") (pinfunction "1_8") (pintype "passive"))
      (node (ref "P1BIAS") (pin "3") (pinfunction "3_3") (pintype "passive"))
      (node (ref "P2BIAS") (pin "3") (pinfunction "3_3") (pintype "passive"))
      (node (ref "P3BIAS") (pin "3") (pinfunction "3_3") (pintype "passive"))
      (node (ref "P4BIAS") (pin "3") (pinfunction "3_3") (pintype "passive"))
    )
    (net (code "137") (name "VREF5-8") (class "Default")
      (node (ref "J29") (pin "3") (pinfunction "1_3") (pintype "passive"))
      (node (ref "J29") (pin "4") (pinfunction "1_4") (pintype "passive"))
      (node (ref "P5BIAS") (pin "3") (pinfunction "3_3") (pintype "passive"))
      (node (ref "P6BIAS") (pin "3") (pinfunction "3_3") (pintype "passive"))
      (node (ref "P7BIAS") (pin "3") (pinfunction "3_3") (pintype "passive"))
      (node (ref "P8BIAS") (pin "3") (pinfunction "3_3") (pintype "passive"))
    )
    (net (code "138") (name "unconnected-(J26B-1-Pad2)") (class "Default")
      (node (ref "J26") (pin "2") (pinfunction "1_2") (pintype "passive"))
    )
    (net (code "139") (name "unconnected-(J26C-1-Pad3)") (class "Default")
      (node (ref "J26") (pin "3") (pinfunction "1_3") (pintype "passive"))
    )
    (net (code "140") (name "unconnected-(J26F-1-Pad6)") (class "Default")
      (node (ref "J26") (pin "6") (pinfunction "1_6") (pintype "passive"))
    )
    (net (code "141") (name "unconnected-(J26G-1-Pad7)") (class "Default")
      (node (ref "J26") (pin "7") (pinfunction "1_7") (pintype "passive"))
    )
    (net (code "142") (name "unconnected-(J26H-1-Pad8)") (class "Default")
      (node (ref "J26") (pin "8") (pinfunction "1_8") (pintype "passive"))
    )
    (net (code "143") (name "unconnected-(J28-Pad1)") (class "Default")
      (node (ref "J28") (pin "1") (pinfunction "1_1") (pintype "passive"))
    )
    (net (code "144") (name "unconnected-(J28B-1-Pad2)") (class "Default")
      (node (ref "J28") (pin "2") (pinfunction "1_2") (pintype "passive"))
    )
    (net (code "145") (name "unconnected-(J28C-1-Pad3)") (class "Default")
      (node (ref "J28") (pin "3") (pinfunction "1_3") (pintype "passive"))
    )
    (net (code "146") (name "unconnected-(J28D-1-Pad4)") (class "Default")
      (node (ref "J28") (pin "4") (pinfunction "1_4") (pintype "passive"))
    )
    (net (code "147") (name "unconnected-(J28E-1-Pad5)") (class "Default")
      (node (ref "J28") (pin "5") (pinfunction "1_5") (pintype "passive"))
    )
    (net (code "148") (name "unconnected-(J28F-1-Pad6)") (class "Default")
      (node (ref "J28") (pin "6") (pinfunction "1_6") (pintype "passive"))
    )
    (net (code "149") (name "unconnected-(J28G-1-Pad7)") (class "Default")
      (node (ref "J28") (pin "7") (pinfunction "1_7") (pintype "passive"))
    )
    (net (code "150") (name "unconnected-(J28H-1-Pad8)") (class "Default")
      (node (ref "J28") (pin "8") (pinfunction "1_8") (pintype "passive"))
    )
    (net (code "151") (name "unconnected-(J29-Pad1)") (class "Default")
      (node (ref "J29") (pin "1") (pinfunction "1_1") (pintype "passive"))
    )
    (net (code "152") (name "unconnected-(J29B-1-Pad2)") (class "Default")
      (node (ref "J29") (pin "2") (pinfunction "1_2") (pintype "passive"))
    )
    (net (code "153") (name "unconnected-(J29E-1-Pad5)") (class "Default")
      (node (ref "J29") (pin "5") (pinfunction "1_5") (pintype "passive"))
    )
    (net (code "154") (name "unconnected-(J29F-1-Pad6)") (class "Default")
      (node (ref "J29") (pin "6") (pinfunction "1_6") (pintype "passive"))
    )
    (net (code "155") (name "unconnected-(PAD7-P-Pad1)") (class "Default")
      (node (ref "PAD7") (pin "1") (pinfunction "P_1") (pintype "passive"))
    )
    (net (code "156") (name "unconnected-(PAD9-P-Pad1)") (class "Default")
      (node (ref "PAD9") (pin "1") (pinfunction "P_1") (pintype "passive"))
    )
  )
)
